# dbt_shield_v2_v23.net
KiCad netlist of a schematic drawn in EAGLE
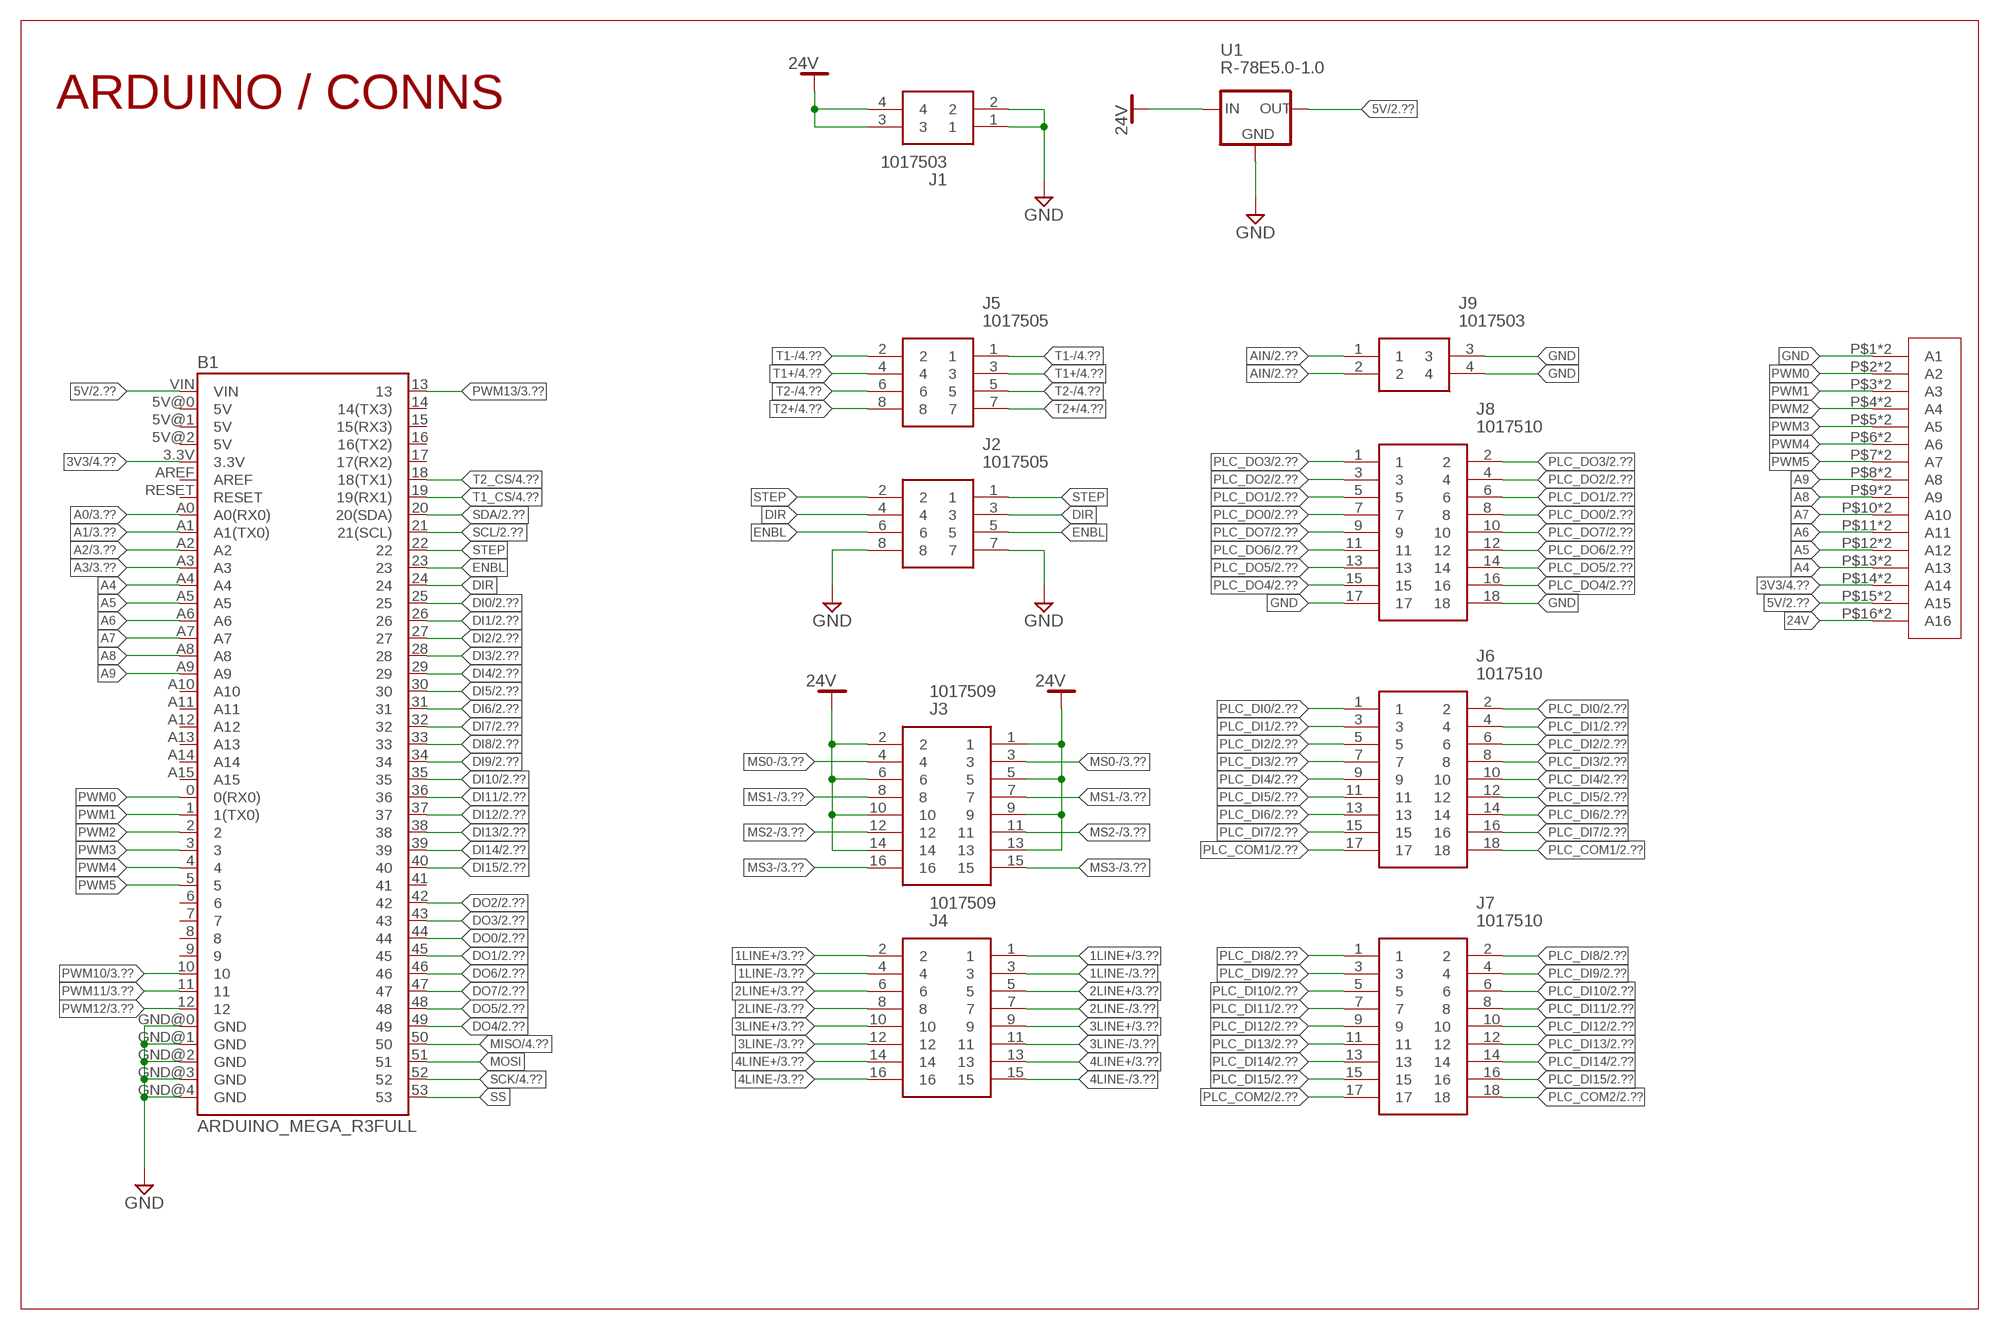
[diagram p0: schematic, sheet 1]
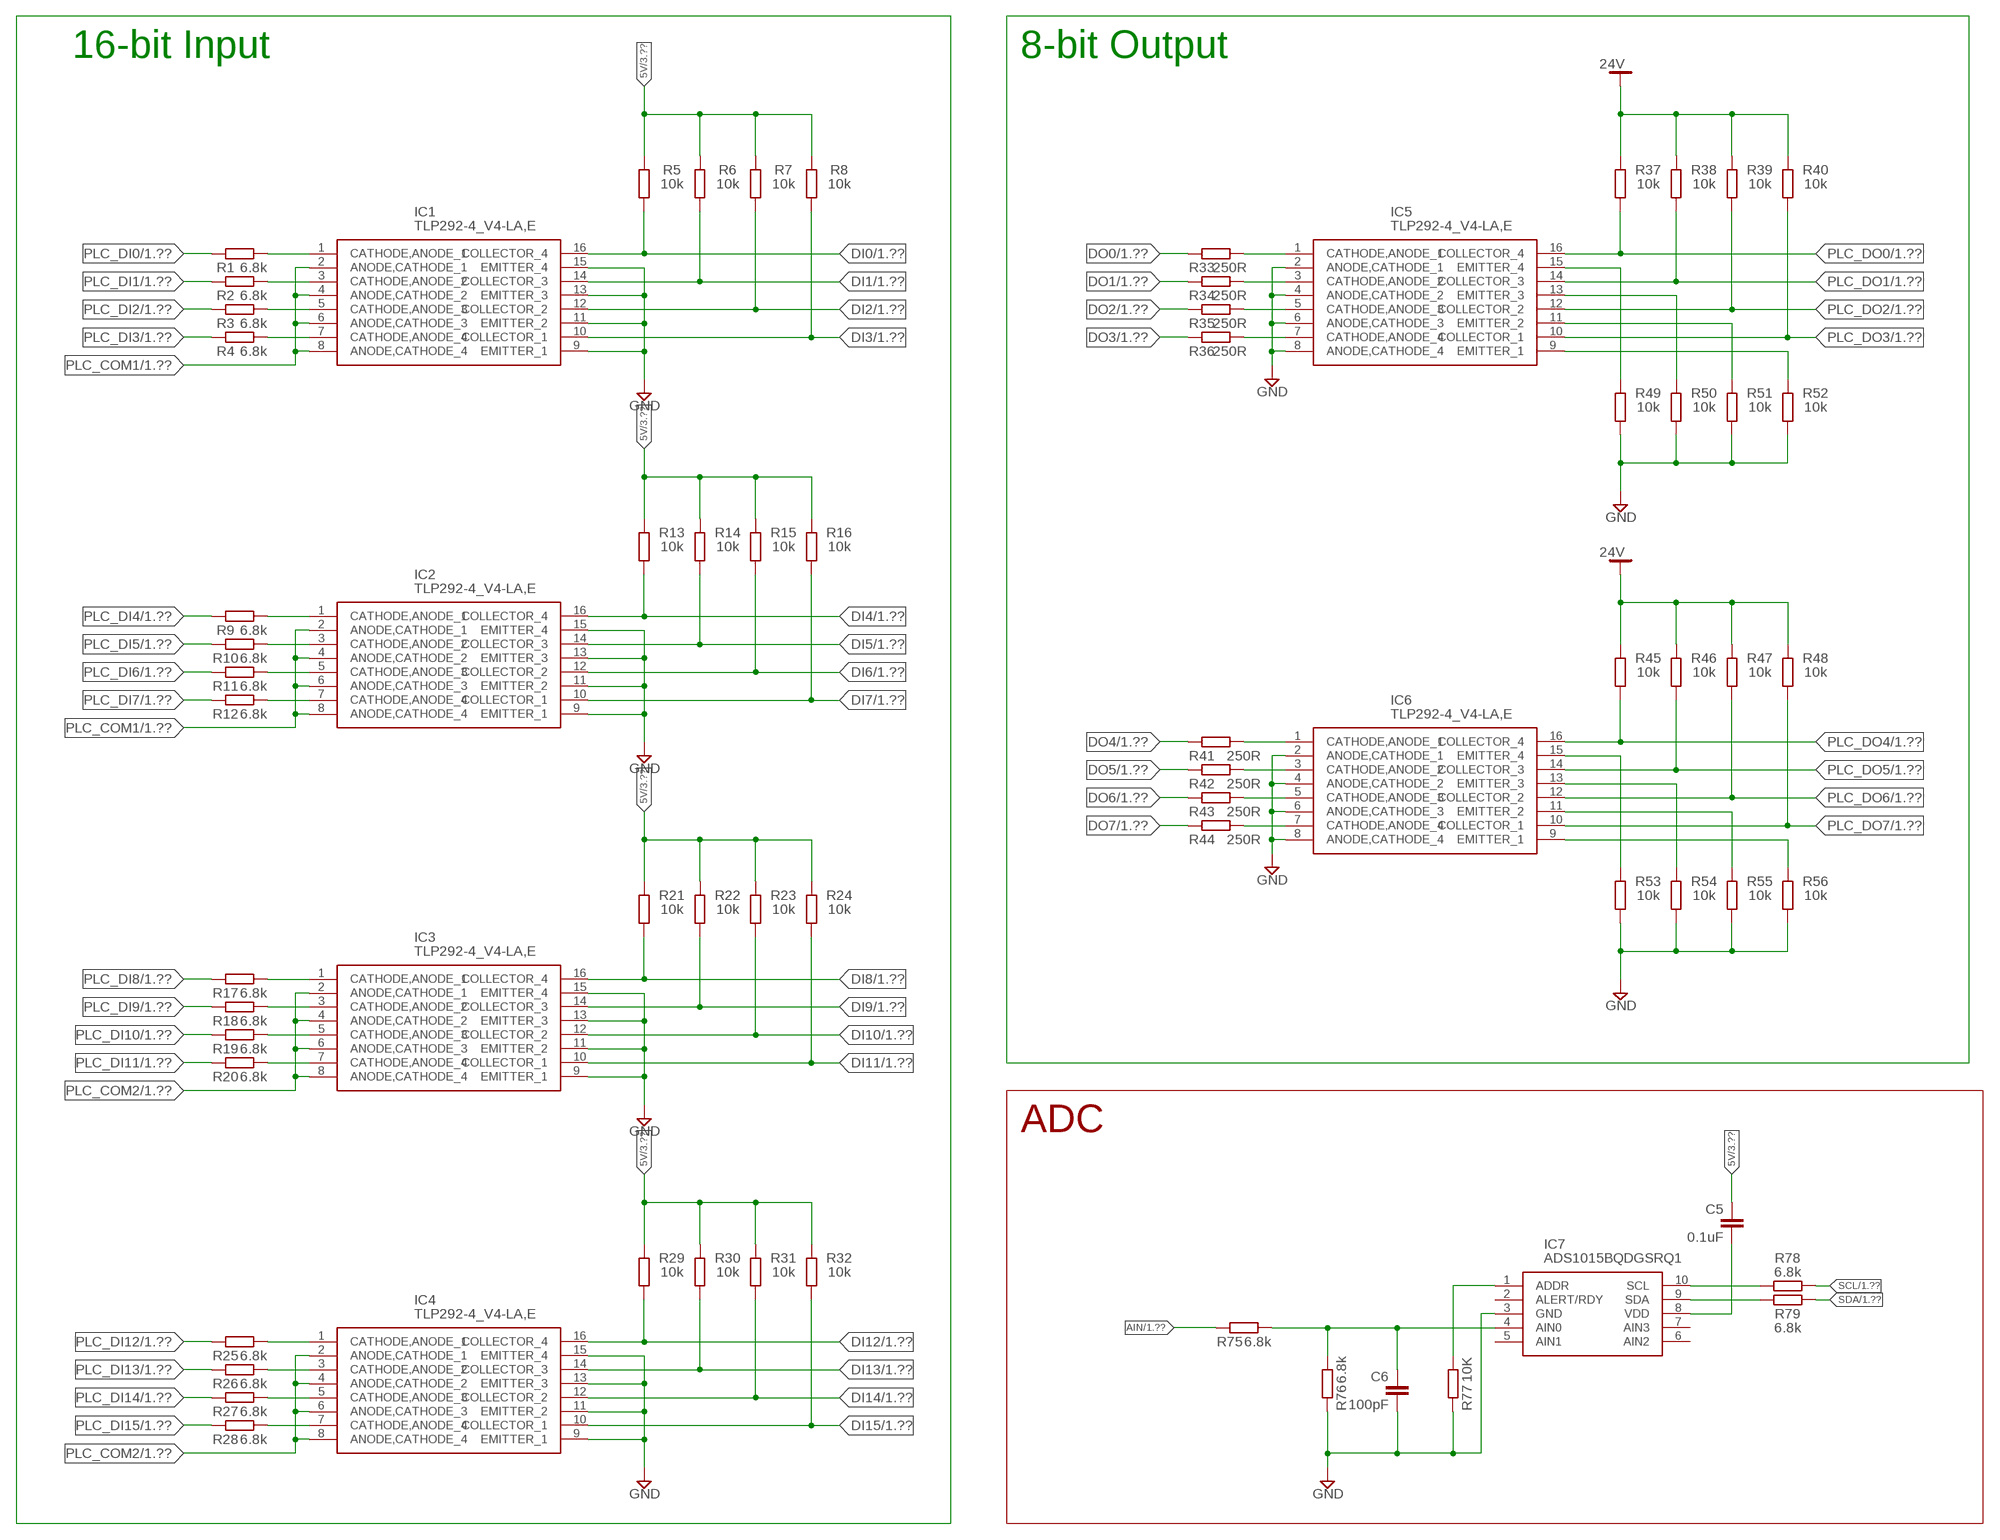
[diagram p1: schematic, sheet 2]
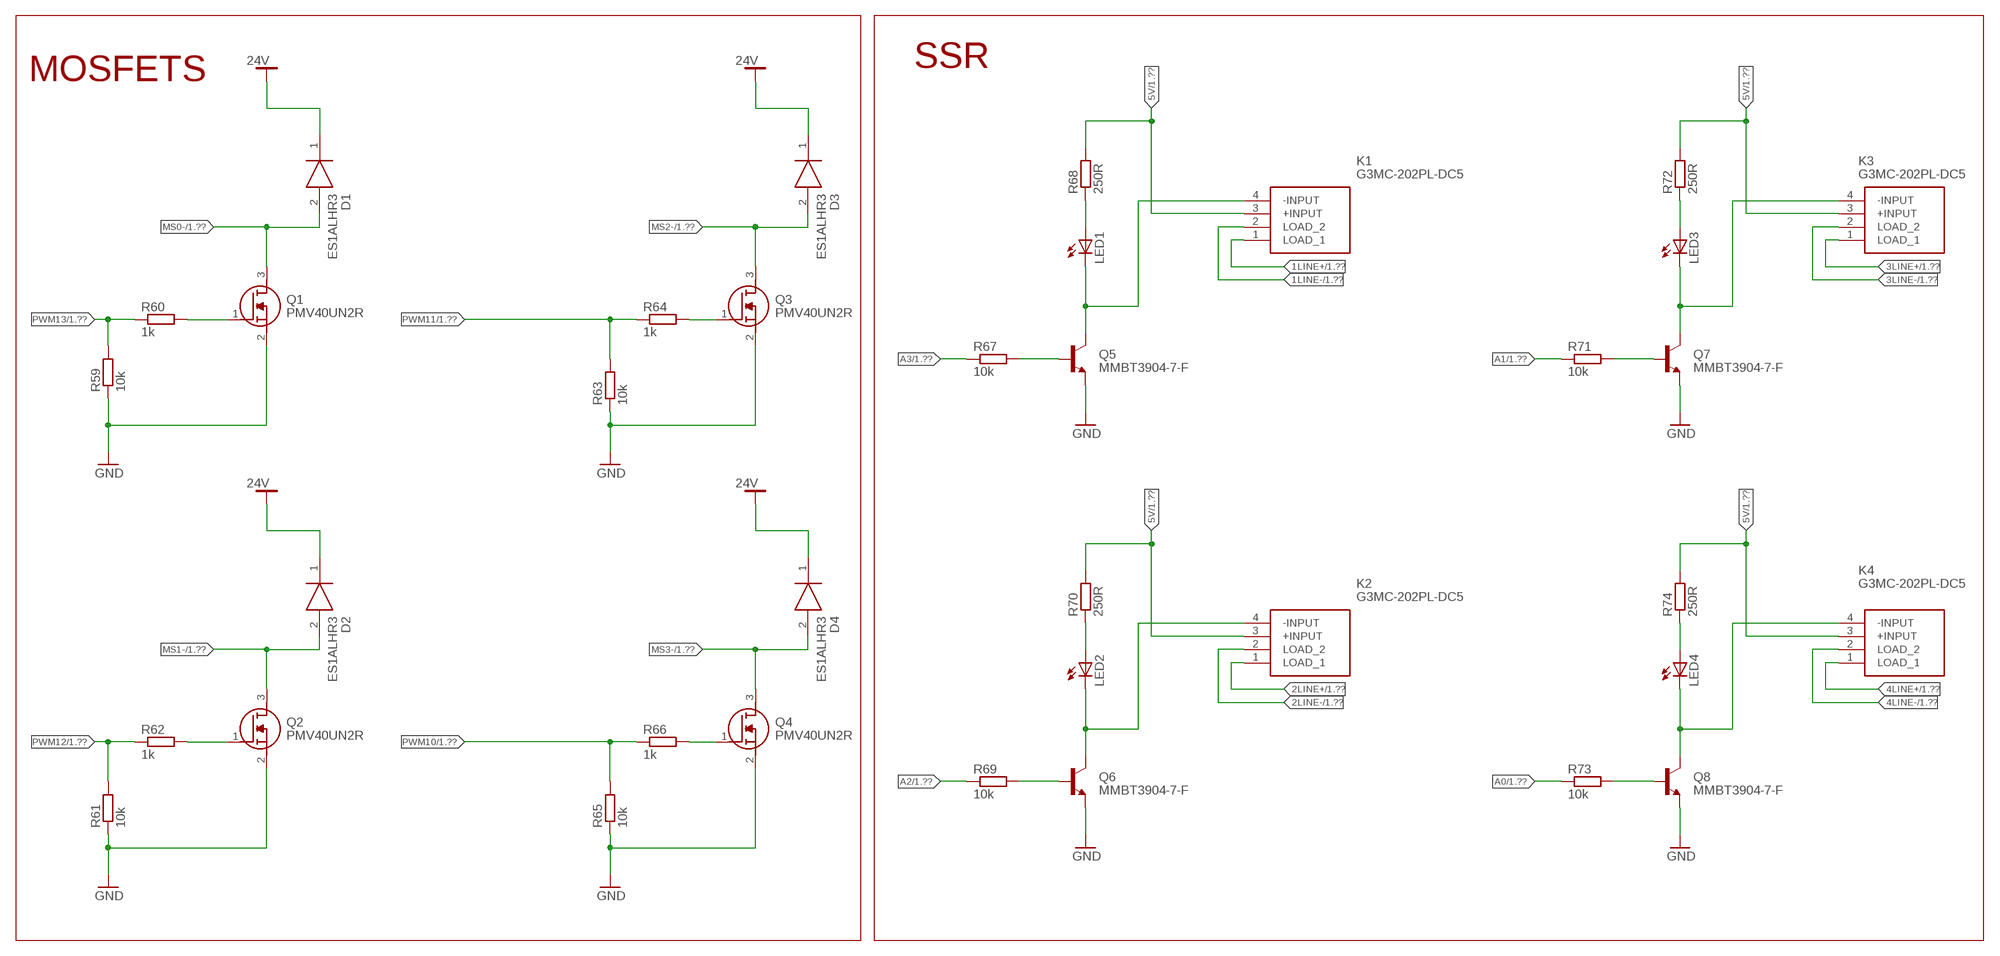
[diagram p2: schematic, sheet 3]
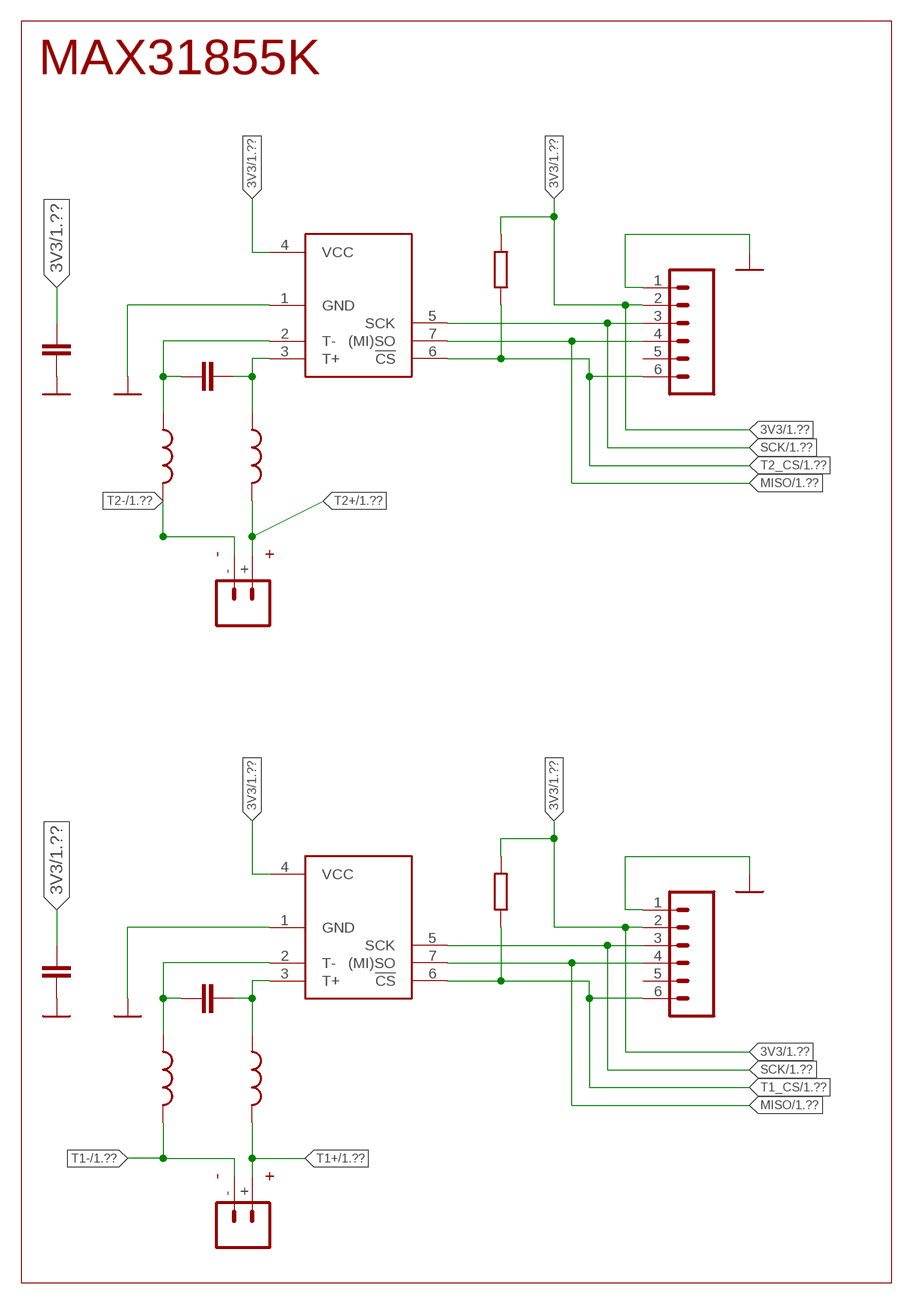
[diagram p3: schematic, sheet 4]

(export (version "E")
  (design (tool "Eeschema 10.0.6"))
  (components
    (comp (ref "C1")
      (value "0.1uF")
      (footprint "eagle-import:CAPC3216X135")
      (libsource (lib "eagle-import") (part "CCHIP-1206(3216-METRIC)_"))
    )
    (comp (ref "C2")
      (value "10 nF")
      (footprint "eagle-import:CAPC3216X135")
      (libsource (lib "eagle-import") (part "CCHIP-1206(3216-METRIC)_"))
    )
    (comp (ref "C3")
      (value "0.1uF")
      (footprint "eagle-import:CAPC3216X135")
      (libsource (lib "eagle-import") (part "CCHIP-1206(3216-METRIC)_"))
    )
    (comp (ref "C4")
      (value "10 nF")
      (footprint "eagle-import:CAPC3216X135")
      (libsource (lib "eagle-import") (part "CCHIP-1206(3216-METRIC)_"))
    )
    (comp (ref "JP1")
      (value "DNP")
      (footprint "eagle-import:1X06")
      (libsource (lib "eagle-import") (part "M06SILK_FEMALE_PTH"))
    )
    (comp (ref "JP2")
      (value "PCB_THERMOCOUPLE")
      (footprint "eagle-import:PCC-SMP")
      (libsource (lib "eagle-import") (part "PCB_THERMOCOUPLE"))
    )
    (comp (ref "JP3")
      (value "DNP")
      (footprint "eagle-import:1X06")
      (libsource (lib "eagle-import") (part "M06SILK_FEMALE_PTH"))
    )
    (comp (ref "JP4")
      (value "PCB_THERMOCOUPLE")
      (footprint "eagle-import:PCC-SMP")
      (libsource (lib "eagle-import") (part "PCB_THERMOCOUPLE"))
    )
    (comp (ref "L1")
      (value "470 OHM")
      (footprint "eagle-import:INDC3216X190")
      (fields (field (name "PROD_ID") "NDUC-12579"))
      (libsource (lib "eagle-import") (part "LCHIP-1206(3216-METRIC)_"))
    )
    (comp (ref "L2")
      (value "470 OHM")
      (footprint "eagle-import:INDC3216X190")
      (fields (field (name "PROD_ID") "NDUC-12579"))
      (libsource (lib "eagle-import") (part "LCHIP-1206(3216-METRIC)_"))
    )
    (comp (ref "L3")
      (value "470 OHM")
      (footprint "eagle-import:INDC3216X190")
      (fields (field (name "PROD_ID") "NDUC-12579"))
      (libsource (lib "eagle-import") (part "LCHIP-1206(3216-METRIC)_"))
    )
    (comp (ref "L4")
      (value "470 OHM")
      (footprint "eagle-import:INDC3216X190")
      (fields (field (name "PROD_ID") "NDUC-12579"))
      (libsource (lib "eagle-import") (part "LCHIP-1206(3216-METRIC)_"))
    )
    (comp (ref "R57")
      (value "10k")
      (footprint "eagle-import:RESC3216X70")
      (libsource (lib "eagle-import") (part "RCHIP-1206(3216-METRIC)_"))
    )
    (comp (ref "R58")
      (value "10k")
      (footprint "eagle-import:RESC3216X70")
      (libsource (lib "eagle-import") (part "RCHIP-1206(3216-METRIC)_"))
    )
    (comp (ref "U2")
      (value "MAX31855K")
      (footprint "eagle-import:SOIC8")
      (fields (field (name "PROD_ID") "IC-12578"))
      (libsource (lib "eagle-import") (part "MAX31855K"))
    )
    (comp (ref "U3")
      (value "MAX31855K")
      (footprint "eagle-import:SOIC8")
      (fields (field (name "PROD_ID") "IC-12578"))
      (libsource (lib "eagle-import") (part "MAX31855K"))
    )
    (comp (ref "C5")
      (value "0.1uF")
      (footprint "eagle-import:CAPC3216X135")
      (libsource (lib "eagle-import") (part "CCHIP-1206(3216-METRIC)_"))
    )
    (comp (ref "C6")
      (value "100pF")
      (footprint "eagle-import:CAPC3216X135")
      (libsource (lib "eagle-import") (part "CCHIP-1206(3216-METRIC)_"))
    )
    (comp (ref "IC1")
      (value "TLP292-4_V4-LA,E")
      (footprint "eagle-import:SOIC127P700X230-16N")
      (fields
        (field (name "MANUFACTURER_PART_NUMBER") "TLP292-4(V4-LA,E")
        (field (name "MOUSER_PART_NUMBER") "757-TLP292-4V4-LAE")
      )
      (libsource (lib "eagle-import") (part "TLP292-4_V4-LA,E"))
    )
    (comp (ref "IC2")
      (value "TLP292-4_V4-LA,E")
      (footprint "eagle-import:SOIC127P700X230-16N")
      (fields
        (field (name "MANUFACTURER_PART_NUMBER") "TLP292-4(V4-LA,E")
        (field (name "MOUSER_PART_NUMBER") "757-TLP292-4V4-LAE")
      )
      (libsource (lib "eagle-import") (part "TLP292-4_V4-LA,E"))
    )
    (comp (ref "IC3")
      (value "TLP292-4_V4-LA,E")
      (footprint "eagle-import:SOIC127P700X230-16N")
      (fields
        (field (name "MANUFACTURER_PART_NUMBER") "TLP292-4(V4-LA,E")
        (field (name "MOUSER_PART_NUMBER") "757-TLP292-4V4-LAE")
      )
      (libsource (lib "eagle-import") (part "TLP292-4_V4-LA,E"))
    )
    (comp (ref "IC4")
      (value "TLP292-4_V4-LA,E")
      (footprint "eagle-import:SOIC127P700X230-16N")
      (fields
        (field (name "MANUFACTURER_PART_NUMBER") "TLP292-4(V4-LA,E")
        (field (name "MOUSER_PART_NUMBER") "757-TLP292-4V4-LAE")
      )
      (libsource (lib "eagle-import") (part "TLP292-4_V4-LA,E"))
    )
    (comp (ref "IC5")
      (value "TLP292-4_V4-LA,E")
      (footprint "eagle-import:SOIC127P700X230-16N")
      (fields
        (field (name "MANUFACTURER_PART_NUMBER") "TLP292-4(V4-LA,E")
        (field (name "MOUSER_PART_NUMBER") "757-TLP292-4V4-LAE")
      )
      (libsource (lib "eagle-import") (part "TLP292-4_V4-LA,E"))
    )
    (comp (ref "IC6")
      (value "TLP292-4_V4-LA,E")
      (footprint "eagle-import:SOIC127P700X230-16N")
      (fields
        (field (name "MANUFACTURER_PART_NUMBER") "TLP292-4(V4-LA,E")
        (field (name "MOUSER_PART_NUMBER") "757-TLP292-4V4-LAE")
      )
      (libsource (lib "eagle-import") (part "TLP292-4_V4-LA,E"))
    )
    (comp (ref "IC7")
      (value "ADS1015BQDGSRQ1")
      (footprint "eagle-import:SOP50P490X110-10N")
      (fields (field (name "MOUSER_PART_NUMBER") "595-ADS1015BQDGSRQ1"))
      (libsource (lib "eagle-import") (part "ADS1015BQDGSRQ1"))
    )
    (comp (ref "R1")
      (value "6.8k")
      (footprint "eagle-import:RESC3216X70")
      (libsource (lib "eagle-import") (part "RCHIP-1206(3216-METRIC)_"))
    )
    (comp (ref "R2")
      (value "6.8k")
      (footprint "eagle-import:RESC3216X70")
      (libsource (lib "eagle-import") (part "RCHIP-1206(3216-METRIC)_"))
    )
    (comp (ref "R3")
      (value "6.8k")
      (footprint "eagle-import:RESC3216X70")
      (libsource (lib "eagle-import") (part "RCHIP-1206(3216-METRIC)_"))
    )
    (comp (ref "R4")
      (value "6.8k")
      (footprint "eagle-import:RESC3216X70")
      (libsource (lib "eagle-import") (part "RCHIP-1206(3216-METRIC)_"))
    )
    (comp (ref "R5")
      (value "10k")
      (footprint "eagle-import:RESC3216X70")
      (libsource (lib "eagle-import") (part "RCHIP-1206(3216-METRIC)_"))
    )
    (comp (ref "R6")
      (value "10k")
      (footprint "eagle-import:RESC3216X70")
      (libsource (lib "eagle-import") (part "RCHIP-1206(3216-METRIC)_"))
    )
    (comp (ref "R7")
      (value "10k")
      (footprint "eagle-import:RESC3216X70")
      (libsource (lib "eagle-import") (part "RCHIP-1206(3216-METRIC)_"))
    )
    (comp (ref "R8")
      (value "10k")
      (footprint "eagle-import:RESC3216X70")
      (libsource (lib "eagle-import") (part "RCHIP-1206(3216-METRIC)_"))
    )
    (comp (ref "R9")
      (value "6.8k")
      (footprint "eagle-import:RESC3216X70")
      (libsource (lib "eagle-import") (part "RCHIP-1206(3216-METRIC)_"))
    )
    (comp (ref "R10")
      (value "6.8k")
      (footprint "eagle-import:RESC3216X70")
      (libsource (lib "eagle-import") (part "RCHIP-1206(3216-METRIC)_"))
    )
    (comp (ref "R11")
      (value "6.8k")
      (footprint "eagle-import:RESC3216X70")
      (libsource (lib "eagle-import") (part "RCHIP-1206(3216-METRIC)_"))
    )
    (comp (ref "R12")
      (value "6.8k")
      (footprint "eagle-import:RESC3216X70")
      (libsource (lib "eagle-import") (part "RCHIP-1206(3216-METRIC)_"))
    )
    (comp (ref "R13")
      (value "10k")
      (footprint "eagle-import:RESC3216X70")
      (libsource (lib "eagle-import") (part "RCHIP-1206(3216-METRIC)_"))
    )
    (comp (ref "R14")
      (value "10k")
      (footprint "eagle-import:RESC3216X70")
      (libsource (lib "eagle-import") (part "RCHIP-1206(3216-METRIC)_"))
    )
    (comp (ref "R15")
      (value "10k")
      (footprint "eagle-import:RESC3216X70")
      (libsource (lib "eagle-import") (part "RCHIP-1206(3216-METRIC)_"))
    )
    (comp (ref "R16")
      (value "10k")
      (footprint "eagle-import:RESC3216X70")
      (libsource (lib "eagle-import") (part "RCHIP-1206(3216-METRIC)_"))
    )
    (comp (ref "R17")
      (value "6.8k")
      (footprint "eagle-import:RESC3216X70")
      (libsource (lib "eagle-import") (part "RCHIP-1206(3216-METRIC)_"))
    )
    (comp (ref "R18")
      (value "6.8k")
      (footprint "eagle-import:RESC3216X70")
      (libsource (lib "eagle-import") (part "RCHIP-1206(3216-METRIC)_"))
    )
    (comp (ref "R19")
      (value "6.8k")
      (footprint "eagle-import:RESC3216X70")
      (libsource (lib "eagle-import") (part "RCHIP-1206(3216-METRIC)_"))
    )
    (comp (ref "R20")
      (value "6.8k")
      (footprint "eagle-import:RESC3216X70")
      (libsource (lib "eagle-import") (part "RCHIP-1206(3216-METRIC)_"))
    )
    (comp (ref "R21")
      (value "10k")
      (footprint "eagle-import:RESC3216X70")
      (libsource (lib "eagle-import") (part "RCHIP-1206(3216-METRIC)_"))
    )
    (comp (ref "R22")
      (value "10k")
      (footprint "eagle-import:RESC3216X70")
      (libsource (lib "eagle-import") (part "RCHIP-1206(3216-METRIC)_"))
    )
    (comp (ref "R23")
      (value "10k")
      (footprint "eagle-import:RESC3216X70")
      (libsource (lib "eagle-import") (part "RCHIP-1206(3216-METRIC)_"))
    )
    (comp (ref "R24")
      (value "10k")
      (footprint "eagle-import:RESC3216X70")
      (libsource (lib "eagle-import") (part "RCHIP-1206(3216-METRIC)_"))
    )
    (comp (ref "R25")
      (value "6.8k")
      (footprint "eagle-import:RESC3216X70")
      (libsource (lib "eagle-import") (part "RCHIP-1206(3216-METRIC)_"))
    )
    (comp (ref "R26")
      (value "6.8k")
      (footprint "eagle-import:RESC3216X70")
      (libsource (lib "eagle-import") (part "RCHIP-1206(3216-METRIC)_"))
    )
    (comp (ref "R27")
      (value "6.8k")
      (footprint "eagle-import:RESC3216X70")
      (libsource (lib "eagle-import") (part "RCHIP-1206(3216-METRIC)_"))
    )
    (comp (ref "R28")
      (value "6.8k")
      (footprint "eagle-import:RESC3216X70")
      (libsource (lib "eagle-import") (part "RCHIP-1206(3216-METRIC)_"))
    )
    (comp (ref "R29")
      (value "10k")
      (footprint "eagle-import:RESC3216X70")
      (libsource (lib "eagle-import") (part "RCHIP-1206(3216-METRIC)_"))
    )
    (comp (ref "R30")
      (value "10k")
      (footprint "eagle-import:RESC3216X70")
      (libsource (lib "eagle-import") (part "RCHIP-1206(3216-METRIC)_"))
    )
    (comp (ref "R31")
      (value "10k")
      (footprint "eagle-import:RESC3216X70")
      (libsource (lib "eagle-import") (part "RCHIP-1206(3216-METRIC)_"))
    )
    (comp (ref "R32")
      (value "10k")
      (footprint "eagle-import:RESC3216X70")
      (libsource (lib "eagle-import") (part "RCHIP-1206(3216-METRIC)_"))
    )
    (comp (ref "R33")
      (value "250R")
      (footprint "eagle-import:RESC3216X70")
      (libsource (lib "eagle-import") (part "RCHIP-1206(3216-METRIC)_"))
    )
    (comp (ref "R34")
      (value "250R")
      (footprint "eagle-import:RESC3216X70")
      (libsource (lib "eagle-import") (part "RCHIP-1206(3216-METRIC)_"))
    )
    (comp (ref "R35")
      (value "250R")
      (footprint "eagle-import:RESC3216X70")
      (libsource (lib "eagle-import") (part "RCHIP-1206(3216-METRIC)_"))
    )
    (comp (ref "R36")
      (value "250R")
      (footprint "eagle-import:RESC3216X70")
      (libsource (lib "eagle-import") (part "RCHIP-1206(3216-METRIC)_"))
    )
    (comp (ref "R37")
      (value "10k")
      (footprint "eagle-import:RESC3216X70")
      (libsource (lib "eagle-import") (part "RCHIP-1206(3216-METRIC)_"))
    )
    (comp (ref "R38")
      (value "10k")
      (footprint "eagle-import:RESC3216X70")
      (libsource (lib "eagle-import") (part "RCHIP-1206(3216-METRIC)_"))
    )
    (comp (ref "R39")
      (value "10k")
      (footprint "eagle-import:RESC3216X70")
      (libsource (lib "eagle-import") (part "RCHIP-1206(3216-METRIC)_"))
    )
    (comp (ref "R40")
      (value "10k")
      (footprint "eagle-import:RESC3216X70")
      (libsource (lib "eagle-import") (part "RCHIP-1206(3216-METRIC)_"))
    )
    (comp (ref "R41")
      (value "250R")
      (footprint "eagle-import:RESC3216X70")
      (libsource (lib "eagle-import") (part "RCHIP-1206(3216-METRIC)_"))
    )
    (comp (ref "R42")
      (value "250R")
      (footprint "eagle-import:RESC3216X70")
      (libsource (lib "eagle-import") (part "RCHIP-1206(3216-METRIC)_"))
    )
    (comp (ref "R43")
      (value "250R")
      (footprint "eagle-import:RESC3216X70")
      (libsource (lib "eagle-import") (part "RCHIP-1206(3216-METRIC)_"))
    )
    (comp (ref "R44")
      (value "250R")
      (footprint "eagle-import:RESC3216X70")
      (libsource (lib "eagle-import") (part "RCHIP-1206(3216-METRIC)_"))
    )
    (comp (ref "R45")
      (value "10k")
      (footprint "eagle-import:RESC3216X70")
      (libsource (lib "eagle-import") (part "RCHIP-1206(3216-METRIC)_"))
    )
    (comp (ref "R46")
      (value "10k")
      (footprint "eagle-import:RESC3216X70")
      (libsource (lib "eagle-import") (part "RCHIP-1206(3216-METRIC)_"))
    )
    (comp (ref "R47")
      (value "10k")
      (footprint "eagle-import:RESC3216X70")
      (libsource (lib "eagle-import") (part "RCHIP-1206(3216-METRIC)_"))
    )
    (comp (ref "R48")
      (value "10k")
      (footprint "eagle-import:RESC3216X70")
      (libsource (lib "eagle-import") (part "RCHIP-1206(3216-METRIC)_"))
    )
    (comp (ref "R49")
      (value "10k")
      (footprint "eagle-import:RESC3216X70")
      (libsource (lib "eagle-import") (part "RCHIP-1206(3216-METRIC)_"))
    )
    (comp (ref "R50")
      (value "10k")
      (footprint "eagle-import:RESC3216X70")
      (libsource (lib "eagle-import") (part "RCHIP-1206(3216-METRIC)_"))
    )
    (comp (ref "R51")
      (value "10k")
      (footprint "eagle-import:RESC3216X70")
      (libsource (lib "eagle-import") (part "RCHIP-1206(3216-METRIC)_"))
    )
    (comp (ref "R52")
      (value "10k")
      (footprint "eagle-import:RESC3216X70")
      (libsource (lib "eagle-import") (part "RCHIP-1206(3216-METRIC)_"))
    )
    (comp (ref "R53")
      (value "10k")
      (footprint "eagle-import:RESC3216X70")
      (libsource (lib "eagle-import") (part "RCHIP-1206(3216-METRIC)_"))
    )
    (comp (ref "R54")
      (value "10k")
      (footprint "eagle-import:RESC3216X70")
      (libsource (lib "eagle-import") (part "RCHIP-1206(3216-METRIC)_"))
    )
    (comp (ref "R55")
      (value "10k")
      (footprint "eagle-import:RESC3216X70")
      (libsource (lib "eagle-import") (part "RCHIP-1206(3216-METRIC)_"))
    )
    (comp (ref "R56")
      (value "10k")
      (footprint "eagle-import:RESC3216X70")
      (libsource (lib "eagle-import") (part "RCHIP-1206(3216-METRIC)_"))
    )
    (comp (ref "R75")
      (value "6.8k")
      (footprint "eagle-import:RESC3216X70")
      (libsource (lib "eagle-import") (part "RCHIP-1206(3216-METRIC)_"))
    )
    (comp (ref "R76")
      (value "6.8k")
      (footprint "eagle-import:RESC3216X70")
      (libsource (lib "eagle-import") (part "RCHIP-1206(3216-METRIC)_"))
    )
    (comp (ref "R77")
      (value "10K")
      (footprint "eagle-import:RESC3216X70")
      (libsource (lib "eagle-import") (part "RCHIP-1206(3216-METRIC)_"))
    )
    (comp (ref "R78")
      (value "6.8k")
      (footprint "eagle-import:RESC3216X70")
      (libsource (lib "eagle-import") (part "RCHIP-1206(3216-METRIC)_"))
    )
    (comp (ref "R79")
      (value "6.8k")
      (footprint "eagle-import:RESC3216X70")
      (libsource (lib "eagle-import") (part "RCHIP-1206(3216-METRIC)_"))
    )
    (comp (ref "B1")
      (value "ARDUINO_MEGA_R3FULL")
      (footprint "eagle-import:ARDUINO_MEGA")
      (libsource (lib "eagle-import") (part "ARDUINO_MEGA_R3FULL"))
    )
    (comp (ref "J1")
      (value "1017503")
      (footprint "eagle-import:1017503")
      (fields (field (name "MOUSER_PART_NUMBER") "651-1017503"))
      (libsource (lib "eagle-import") (part "1017503"))
    )
    (comp (ref "J2")
      (value "1017505")
      (footprint "eagle-import:1017505")
      (fields (field (name "MOUSER_PART_NUMBER") "651-1017505") (field (name "RS_PART_NUMBER") "1753922"))
      (libsource (lib "eagle-import") (part "1017505"))
    )
    (comp (ref "J3")
      (value "1017509")
      (footprint "eagle-import:1017509")
      (fields (field (name "MOUSER_PART_NUMBER") "651-1017509") (field (name "RS_PART_NUMBER") "1753943P"))
      (libsource (lib "eagle-import") (part "1017509"))
    )
    (comp (ref "J4")
      (value "1017509")
      (footprint "eagle-import:1017509")
      (fields (field (name "MOUSER_PART_NUMBER") "651-1017509") (field (name "RS_PART_NUMBER") "1753943P"))
      (libsource (lib "eagle-import") (part "1017509"))
    )
    (comp (ref "J5")
      (value "1017505")
      (footprint "eagle-import:1017505")
      (fields (field (name "MOUSER_PART_NUMBER") "651-1017505") (field (name "RS_PART_NUMBER") "1753922"))
      (libsource (lib "eagle-import") (part "1017505"))
    )
    (comp (ref "J6")
      (value "1017510")
      (footprint "eagle-import:SHDR18W120P870X508_2X9_4652X18")
      (fields (field (name "MOUSER_PART_NUMBER") "651-1017510") (field (name "RS_PART_NUMBER") "1753946P"))
      (libsource (lib "eagle-import") (part "1017510"))
    )
    (comp (ref "J7")
      (value "1017510")
      (footprint "eagle-import:SHDR18W120P870X508_2X9_4652X18")
      (fields (field (name "MOUSER_PART_NUMBER") "651-1017510") (field (name "RS_PART_NUMBER") "1753946P"))
      (libsource (lib "eagle-import") (part "1017510"))
    )
    (comp (ref "J8")
      (value "1017510")
      (footprint "eagle-import:SHDR18W120P870X508_2X9_4652X18")
      (fields (field (name "MOUSER_PART_NUMBER") "651-1017510") (field (name "RS_PART_NUMBER") "1753946P"))
      (libsource (lib "eagle-import") (part "1017510"))
    )
    (comp (ref "J9")
      (value "1017503")
      (footprint "eagle-import:1017503")
      (fields (field (name "MOUSER_PART_NUMBER") "651-1017503"))
      (libsource (lib "eagle-import") (part "1017503"))
    )
    (comp (ref "U$1")
      (value "1861991")
      (footprint "eagle-import:1861991")
      (libsource (lib "eagle-import") (part "1861991"))
    )
    (comp (ref "U1")
      (value "R-78E5.0-1.0")
      (footprint "eagle-import:DC-DC_CONVERTER_78XX")
      (libsource (lib "eagle-import") (part "R-78E5.0-1.0"))
    )
    (comp (ref "D1")
      (value "ES1ALHR3")
      (footprint "eagle-import:SODFL3618X143N")
      (fields (field (name "MOUSER_PART_NUMBER") "821-ES1ALHR3"))
      (libsource (lib "eagle-import") (part "ES1ALHR3"))
    )
    (comp (ref "D2")
      (value "ES1ALHR3")
      (footprint "eagle-import:SODFL3618X143N")
      (fields (field (name "MOUSER_PART_NUMBER") "821-ES1ALHR3"))
      (libsource (lib "eagle-import") (part "ES1ALHR3"))
    )
    (comp (ref "D3")
      (value "ES1ALHR3")
      (footprint "eagle-import:SODFL3618X143N")
      (fields (field (name "MOUSER_PART_NUMBER") "821-ES1ALHR3"))
      (libsource (lib "eagle-import") (part "ES1ALHR3"))
    )
    (comp (ref "D4")
      (value "ES1ALHR3")
      (footprint "eagle-import:SODFL3618X143N")
      (fields (field (name "MOUSER_PART_NUMBER") "821-ES1ALHR3"))
      (libsource (lib "eagle-import") (part "ES1ALHR3"))
    )
    (comp (ref "K1")
      (value "G3MC-202PL-DC5")
      (footprint "eagle-import:G3MC202PLDC5")
      (fields (field (name "MOUSER_PART_NUMBER") "653-G3MC-202PL-DC5"))
      (libsource (lib "eagle-import") (part "G3MC-202PL-DC5"))
    )
    (comp (ref "K2")
      (value "G3MC-202PL-DC5")
      (footprint "eagle-import:G3MC202PLDC5")
      (fields (field (name "MOUSER_PART_NUMBER") "653-G3MC-202PL-DC5"))
      (libsource (lib "eagle-import") (part "G3MC-202PL-DC5"))
    )
    (comp (ref "K3")
      (value "G3MC-202PL-DC5")
      (footprint "eagle-import:G3MC202PLDC5")
      (fields (field (name "MOUSER_PART_NUMBER") "653-G3MC-202PL-DC5"))
      (libsource (lib "eagle-import") (part "G3MC-202PL-DC5"))
    )
    (comp (ref "K4")
      (value "G3MC-202PL-DC5")
      (footprint "eagle-import:G3MC202PLDC5")
      (fields (field (name "MOUSER_PART_NUMBER") "653-G3MC-202PL-DC5"))
      (libsource (lib "eagle-import") (part "G3MC-202PL-DC5"))
    )
    (comp (ref "LED1")
      (value "LEDCHIPLED_1206")
      (footprint "eagle-import:CHIPLED_1206")
      (libsource (lib "eagle-import") (part "LEDCHIPLED_1206"))
    )
    (comp (ref "LED2")
      (value "LEDCHIPLED_1206")
      (footprint "eagle-import:CHIPLED_1206")
      (libsource (lib "eagle-import") (part "LEDCHIPLED_1206"))
    )
    (comp (ref "LED3")
      (value "LEDCHIPLED_1206")
      (footprint "eagle-import:CHIPLED_1206")
      (libsource (lib "eagle-import") (part "LEDCHIPLED_1206"))
    )
    (comp (ref "LED4")
      (value "LEDCHIPLED_1206")
      (footprint "eagle-import:CHIPLED_1206")
      (libsource (lib "eagle-import") (part "LEDCHIPLED_1206"))
    )
    (comp (ref "Q1")
      (value "PMV40UN2R")
      (footprint "eagle-import:SOT95P230X110-3N")
      (fields (field (name "MOUSER_PART_NUMBER") "771-PMV40UN2R") (field (name "RS_PART_NUMBER") "1362196P"))
      (libsource (lib "eagle-import") (part "PMV40UN2R"))
    )
    (comp (ref "Q2")
      (value "PMV40UN2R")
      (footprint "eagle-import:SOT95P230X110-3N")
      (fields (field (name "MOUSER_PART_NUMBER") "771-PMV40UN2R") (field (name "RS_PART_NUMBER") "1362196P"))
      (libsource (lib "eagle-import") (part "PMV40UN2R"))
    )
    (comp (ref "Q3")
      (value "PMV40UN2R")
      (footprint "eagle-import:SOT95P230X110-3N")
      (fields (field (name "MOUSER_PART_NUMBER") "771-PMV40UN2R") (field (name "RS_PART_NUMBER") "1362196P"))
      (libsource (lib "eagle-import") (part "PMV40UN2R"))
    )
    (comp (ref "Q4")
      (value "PMV40UN2R")
      (footprint "eagle-import:SOT95P230X110-3N")
      (fields (field (name "MOUSER_PART_NUMBER") "771-PMV40UN2R") (field (name "RS_PART_NUMBER") "1362196P"))
      (libsource (lib "eagle-import") (part "PMV40UN2R"))
    )
    (comp (ref "Q5")
      (value "MMBT3904-7-F")
      (footprint "eagle-import:SOT95P230X110-3N1")
      (fields (field (name "MF") "Diodes Inc."))
      (libsource (lib "eagle-import") (part "MMBT3904-7-F"))
    )
    (comp (ref "Q6")
      (value "MMBT3904-7-F")
      (footprint "eagle-import:SOT95P230X110-3N1")
      (fields (field (name "MF") "Diodes Inc."))
      (libsource (lib "eagle-import") (part "MMBT3904-7-F"))
    )
    (comp (ref "Q7")
      (value "MMBT3904-7-F")
      (footprint "eagle-import:SOT95P230X110-3N1")
      (fields (field (name "MF") "Diodes Inc."))
      (libsource (lib "eagle-import") (part "MMBT3904-7-F"))
    )
    (comp (ref "Q8")
      (value "MMBT3904-7-F")
      (footprint "eagle-import:SOT95P230X110-3N1")
      (fields (field (name "MF") "Diodes Inc."))
      (libsource (lib "eagle-import") (part "MMBT3904-7-F"))
    )
    (comp (ref "R59")
      (value "10k")
      (footprint "eagle-import:RESC3216X70")
      (libsource (lib "eagle-import") (part "RCHIP-1206(3216-METRIC)_"))
    )
    (comp (ref "R60")
      (value "1k")
      (footprint "eagle-import:RESC3216X70")
      (libsource (lib "eagle-import") (part "RCHIP-1206(3216-METRIC)_"))
    )
    (comp (ref "R61")
      (value "10k")
      (footprint "eagle-import:RESC3216X70")
      (libsource (lib "eagle-import") (part "RCHIP-1206(3216-METRIC)_"))
    )
    (comp (ref "R62")
      (value "1k")
      (footprint "eagle-import:RESC3216X70")
      (libsource (lib "eagle-import") (part "RCHIP-1206(3216-METRIC)_"))
    )
    (comp (ref "R63")
      (value "10k")
      (footprint "eagle-import:RESC3216X70")
      (libsource (lib "eagle-import") (part "RCHIP-1206(3216-METRIC)_"))
    )
    (comp (ref "R64")
      (value "1k")
      (footprint "eagle-import:RESC3216X70")
      (libsource (lib "eagle-import") (part "RCHIP-1206(3216-METRIC)_"))
    )
    (comp (ref "R65")
      (value "10k")
      (footprint "eagle-import:RESC3216X70")
      (libsource (lib "eagle-import") (part "RCHIP-1206(3216-METRIC)_"))
    )
    (comp (ref "R66")
      (value "1k")
      (footprint "eagle-import:RESC3216X70")
      (libsource (lib "eagle-import") (part "RCHIP-1206(3216-METRIC)_"))
    )
    (comp (ref "R67")
      (value "10k")
      (footprint "eagle-import:RESC3216X70")
      (libsource (lib "eagle-import") (part "RCHIP-1206(3216-METRIC)_"))
    )
    (comp (ref "R68")
      (value "250R")
      (footprint "eagle-import:RESC3216X70")
      (libsource (lib "eagle-import") (part "RCHIP-1206(3216-METRIC)_"))
    )
    (comp (ref "R69")
      (value "10k")
      (footprint "eagle-import:RESC3216X70")
      (libsource (lib "eagle-import") (part "RCHIP-1206(3216-METRIC)_"))
    )
    (comp (ref "R70")
      (value "250R")
      (footprint "eagle-import:RESC3216X70")
      (libsource (lib "eagle-import") (part "RCHIP-1206(3216-METRIC)_"))
    )
    (comp (ref "R71")
      (value "10k")
      (footprint "eagle-import:RESC3216X70")
      (libsource (lib "eagle-import") (part "RCHIP-1206(3216-METRIC)_"))
    )
    (comp (ref "R72")
      (value "250R")
      (footprint "eagle-import:RESC3216X70")
      (libsource (lib "eagle-import") (part "RCHIP-1206(3216-METRIC)_"))
    )
    (comp (ref "R73")
      (value "10k")
      (footprint "eagle-import:RESC3216X70")
      (libsource (lib "eagle-import") (part "RCHIP-1206(3216-METRIC)_"))
    )
    (comp (ref "R74")
      (value "250R")
      (footprint "eagle-import:RESC3216X70")
      (libsource (lib "eagle-import") (part "RCHIP-1206(3216-METRIC)_"))
    )
  )
  (nets
    (net (code "1") (name "1LINE+") (class "Default")
      (node (ref "J4") (pin "1") (pinfunction "1_1") (pintype "bidirectional"))
      (node (ref "J4") (pin "2") (pinfunction "2_2") (pintype "bidirectional"))
      (node (ref "K1") (pin "1") (pinfunction "LOAD_1_1") (pintype "bidirectional"))
    )
    (net (code "2") (name "1LINE-") (class "Default")
      (node (ref "J4") (pin "3") (pinfunction "3_3") (pintype "bidirectional"))
      (node (ref "J4") (pin "4") (pinfunction "4_4") (pintype "bidirectional"))
      (node (ref "K1") (pin "2") (pinfunction "LOAD_2_2") (pintype "bidirectional"))
    )
    (net (code "3") (name "2LINE+") (class "Default")
      (node (ref "J4") (pin "5") (pinfunction "5_5") (pintype "bidirectional"))
      (node (ref "J4") (pin "6") (pinfunction "6_6") (pintype "bidirectional"))
      (node (ref "K2") (pin "1") (pinfunction "LOAD_1_1") (pintype "bidirectional"))
    )
    (net (code "4") (name "2LINE-") (class "Default")
      (node (ref "J4") (pin "7") (pinfunction "7_7") (pintype "bidirectional"))
      (node (ref "J4") (pin "8") (pinfunction "8_8") (pintype "bidirectional"))
      (node (ref "K2") (pin "2") (pinfunction "LOAD_2_2") (pintype "bidirectional"))
    )
    (net (code "5") (name "3LINE+") (class "Default")
      (node (ref "J4") (pin "10") (pinfunction "10_10") (pintype "bidirectional"))
      (node (ref "J4") (pin "9") (pinfunction "9_9") (pintype "bidirectional"))
      (node (ref "K3") (pin "1") (pinfunction "LOAD_1_1") (pintype "bidirectional"))
    )
    (net (code "6") (name "3LINE-") (class "Default")
      (node (ref "J4") (pin "11") (pinfunction "11_11") (pintype "bidirectional"))
      (node (ref "J4") (pin "12") (pinfunction "12_12") (pintype "bidirectional"))
      (node (ref "K3") (pin "2") (pinfunction "LOAD_2_2") (pintype "bidirectional"))
    )
    (net (code "7") (name "3V3") (class "Default")
      (node (ref "B1") (pin "3.3V") (pinfunction "3.3V_3.3V") (pintype "bidirectional"))
      (node (ref "C1") (pin "1") (pinfunction "1_1") (pintype "passive"))
      (node (ref "C3") (pin "1") (pinfunction "1_1") (pintype "passive"))
      (node (ref "JP1") (pin "2") (pinfunction "2_2") (pintype "passive"))
      (node (ref "JP3") (pin "2") (pinfunction "2_2") (pintype "passive"))
      (node (ref "R57") (pin "2") (pinfunction "2_2") (pintype "passive"))
      (node (ref "R58") (pin "2") (pinfunction "2_2") (pintype "passive"))
      (node (ref "U$1") (pin "P$14") (pinfunction "A14_P$14") (pintype "bidirectional"))
      (node (ref "U$1") (pin "P$30") (pinfunction "A14_P$30") (pintype "bidirectional"))
      (node (ref "U2") (pin "4") (pinfunction "VCC_4") (pintype "bidirectional"))
      (node (ref "U3") (pin "4") (pinfunction "VCC_4") (pintype "bidirectional"))
    )
    (net (code "8") (name "4LINE+") (class "Default")
      (node (ref "J4") (pin "13") (pinfunction "13_13") (pintype "bidirectional"))
      (node (ref "J4") (pin "14") (pinfunction "14_14") (pintype "bidirectional"))
      (node (ref "K4") (pin "1") (pinfunction "LOAD_1_1") (pintype "bidirectional"))
    )
    (net (code "9") (name "4LINE-") (class "Default")
      (node (ref "J4") (pin "15") (pinfunction "15_15") (pintype "bidirectional"))
      (node (ref "J4") (pin "16") (pinfunction "16_16") (pintype "bidirectional"))
      (node (ref "K4") (pin "2") (pinfunction "LOAD_2_2") (pintype "bidirectional"))
    )
    (net (code "10") (name "5V") (class "Default")
      (node (ref "B1") (pin "VIN") (pinfunction "VIN_VIN") (pintype "bidirectional"))
      (node (ref "C5") (pin "1") (pinfunction "1_1") (pintype "passive"))
      (node (ref "K1") (pin "3") (pinfunction "+INPUT_3") (pintype "bidirectional"))
      (node (ref "K2") (pin "3") (pinfunction "+INPUT_3") (pintype "bidirectional"))
      (node (ref "K3") (pin "3") (pinfunction "+INPUT_3") (pintype "bidirectional"))
      (node (ref "K4") (pin "3") (pinfunction "+INPUT_3") (pintype "bidirectional"))
      (node (ref "R13") (pin "2") (pinfunction "2_2") (pintype "passive"))
      (node (ref "R14") (pin "2") (pinfunction "2_2") (pintype "passive"))
      (node (ref "R15") (pin "2") (pinfunction "2_2") (pintype "passive"))
      (node (ref "R16") (pin "2") (pinfunction "2_2") (pintype "passive"))
      (node (ref "R21") (pin "2") (pinfunction "2_2") (pintype "passive"))
      (node (ref "R22") (pin "2") (pinfunction "2_2") (pintype "passive"))
      (node (ref "R23") (pin "2") (pinfunction "2_2") (pintype "passive"))
      (node (ref "R24") (pin "2") (pinfunction "2_2") (pintype "passive"))
      (node (ref "R29") (pin "2") (pinfunction "2_2") (pintype "passive"))
      (node (ref "R30") (pin "2") (pinfunction "2_2") (pintype "passive"))
      (node (ref "R31") (pin "2") (pinfunction "2_2") (pintype "passive"))
      (node (ref "R32") (pin "2") (pinfunction "2_2") (pintype "passive"))
      (node (ref "R5") (pin "2") (pinfunction "2_2") (pintype "passive"))
      (node (ref "R6") (pin "2") (pinfunction "2_2") (pintype "passive"))
      (node (ref "R68") (pin "2") (pinfunction "2_2") (pintype "passive"))
      (node (ref "R7") (pin "2") (pinfunction "2_2") (pintype "passive"))
      (node (ref "R70") (pin "2") (pinfunction "2_2") (pintype "passive"))
      (node (ref "R72") (pin "2") (pinfunction "2_2") (pintype "passive"))
      (node (ref "R74") (pin "2") (pinfunction "2_2") (pintype "passive"))
      (node (ref "R8") (pin "2") (pinfunction "2_2") (pintype "passive"))
      (node (ref "U$1") (pin "P$15") (pinfunction "A15_P$15") (pintype "bidirectional"))
      (node (ref "U$1") (pin "P$31") (pinfunction "A15_P$31") (pintype "bidirectional"))
      (node (ref "U1") (pin "VOUT") (pinfunction "OUT_VOUT") (pintype "passive"))
    )
    (net (code "11") (name "24V") (class "Default")
      (node (ref "D1") (pin "1") (pinfunction "K_1") (pintype "bidirectional"))
      (node (ref "D2") (pin "1") (pinfunction "K_1") (pintype "bidirectional"))
      (node (ref "D3") (pin "1") (pinfunction "K_1") (pintype "bidirectional"))
      (node (ref "D4") (pin "1") (pinfunction "K_1") (pintype "bidirectional"))
      (node (ref "J1") (pin "3") (pinfunction "3_3") (pintype "bidirectional"))
      (node (ref "J1") (pin "4") (pinfunction "4_4") (pintype "bidirectional"))
      (node (ref "J3") (pin "1") (pinfunction "1_1") (pintype "bidirectional"))
      (node (ref "J3") (pin "10") (pinfunction "10_10") (pintype "bidirectional"))
      (node (ref "J3") (pin "13") (pinfunction "13_13") (pintype "bidirectional"))
      (node (ref "J3") (pin "14") (pinfunction "14_14") (pintype "bidirectional"))
      (node (ref "J3") (pin "2") (pinfunction "2_2") (pintype "bidirectional"))
      (node (ref "J3") (pin "5") (pinfunction "5_5") (pintype "bidirectional"))
      (node (ref "J3") (pin "6") (pinfunction "6_6") (pintype "bidirectional"))
      (node (ref "J3") (pin "9") (pinfunction "9_9") (pintype "bidirectional"))
      (node (ref "R37") (pin "2") (pinfunction "2_2") (pintype "passive"))
      (node (ref "R38") (pin "2") (pinfunction "2_2") (pintype "passive"))
      (node (ref "R39") (pin "2") (pinfunction "2_2") (pintype "passive"))
      (node (ref "R40") (pin "2") (pinfunction "2_2") (pintype "passive"))
      (node (ref "R45") (pin "2") (pinfunction "2_2") (pintype "passive"))
      (node (ref "R46") (pin "2") (pinfunction "2_2") (pintype "passive"))
      (node (ref "R47") (pin "2") (pinfunction "2_2") (pintype "passive"))
      (node (ref "R48") (pin "2") (pinfunction "2_2") (pintype "passive"))
      (node (ref "U$1") (pin "P$16") (pinfunction "A16_P$16") (pintype "bidirectional"))
      (node (ref "U$1") (pin "P$32") (pinfunction "A16_P$32") (pintype "bidirectional"))
      (node (ref "U1") (pin "VIN") (pinfunction "IN_VIN") (pintype "input"))
    )
    (net (code "12") (name "A0") (class "Default")
      (node (ref "B1") (pin "A0") (pinfunction "A0(RX0)_A0") (pintype "bidirectional"))
      (node (ref "R73") (pin "1") (pinfunction "1_1") (pintype "passive"))
    )
    (net (code "13") (name "A1") (class "Default")
      (node (ref "B1") (pin "A1") (pinfunction "A1(TX0)_A1") (pintype "bidirectional"))
      (node (ref "R71") (pin "1") (pinfunction "1_1") (pintype "passive"))
    )
    (net (code "14") (name "A2") (class "Default")
      (node (ref "B1") (pin "A2") (pinfunction "A2_A2") (pintype "bidirectional"))
      (node (ref "R69") (pin "1") (pinfunction "1_1") (pintype "passive"))
    )
    (net (code "15") (name "A3") (class "Default")
      (node (ref "B1") (pin "A3") (pinfunction "A3_A3") (pintype "bidirectional"))
      (node (ref "R67") (pin "1") (pinfunction "1_1") (pintype "passive"))
    )
    (net (code "16") (name "A4") (class "Default")
      (node (ref "B1") (pin "A4") (pinfunction "A4_A4") (pintype "bidirectional"))
      (node (ref "U$1") (pin "P$13") (pinfunction "A13_P$13") (pintype "bidirectional"))
      (node (ref "U$1") (pin "P$29") (pinfunction "A13_P$29") (pintype "bidirectional"))
    )
    (net (code "17") (name "A5") (class "Default")
      (node (ref "B1") (pin "A5") (pinfunction "A5_A5") (pintype "bidirectional"))
      (node (ref "U$1") (pin "P$12") (pinfunction "A12_P$12") (pintype "bidirectional"))
      (node (ref "U$1") (pin "P$28") (pinfunction "A12_P$28") (pintype "bidirectional"))
    )
    (net (code "18") (name "A6") (class "Default")
      (node (ref "B1") (pin "A6") (pinfunction "A6_A6") (pintype "bidirectional"))
      (node (ref "U$1") (pin "P$11") (pinfunction "A11_P$11") (pintype "bidirectional"))
      (node (ref "U$1") (pin "P$27") (pinfunction "A11_P$27") (pintype "bidirectional"))
    )
    (net (code "19") (name "A7") (class "Default")
      (node (ref "B1") (pin "A7") (pinfunction "A7_A7") (pintype "bidirectional"))
      (node (ref "U$1") (pin "P$10") (pinfunction "A10_P$10") (pintype "bidirectional"))
      (node (ref "U$1") (pin "P$26") (pinfunction "A10_P$26") (pintype "bidirectional"))
    )
    (net (code "20") (name "A8") (class "Default")
      (node (ref "B1") (pin "A8") (pinfunction "A8_A8") (pintype "bidirectional"))
      (node (ref "U$1") (pin "P$25") (pinfunction "A9_P$25") (pintype "bidirectional"))
      (node (ref "U$1") (pin "P$9") (pinfunction "A9_P$9") (pintype "bidirectional"))
    )
    (net (code "21") (name "A9") (class "Default")
      (node (ref "B1") (pin "A9") (pinfunction "A9_A9") (pintype "bidirectional"))
      (node (ref "U$1") (pin "P$24") (pinfunction "A8_P$24") (pintype "bidirectional"))
      (node (ref "U$1") (pin "P$8") (pinfunction "A8_P$8") (pintype "bidirectional"))
    )
    (net (code "22") (name "AIN") (class "Default")
      (node (ref "J9") (pin "1") (pinfunction "1_1") (pintype "bidirectional"))
      (node (ref "J9") (pin "2") (pinfunction "2_2") (pintype "bidirectional"))
      (node (ref "R75") (pin "1") (pinfunction "1_1") (pintype "passive"))
    )
    (net (code "23") (name "DI0") (class "Default")
      (node (ref "B1") (pin "25") (pinfunction "25_25") (pintype "bidirectional"))
      (node (ref "IC1") (pin "16") (pinfunction "COLLECTOR_4_16") (pintype "bidirectional"))
      (node (ref "R5") (pin "1") (pinfunction "1_1") (pintype "passive"))
    )
    (net (code "24") (name "DI1") (class "Default")
      (node (ref "B1") (pin "26") (pinfunction "26_26") (pintype "bidirectional"))
      (node (ref "IC1") (pin "14") (pinfunction "COLLECTOR_3_14") (pintype "bidirectional"))
      (node (ref "R6") (pin "1") (pinfunction "1_1") (pintype "passive"))
    )
    (net (code "25") (name "DI2") (class "Default")
      (node (ref "B1") (pin "27") (pinfunction "27_27") (pintype "bidirectional"))
      (node (ref "IC1") (pin "12") (pinfunction "COLLECTOR_2_12") (pintype "bidirectional"))
      (node (ref "R7") (pin "1") (pinfunction "1_1") (pintype "passive"))
    )
    (net (code "26") (name "DI3") (class "Default")
      (node (ref "B1") (pin "28") (pinfunction "28_28") (pintype "bidirectional"))
      (node (ref "IC1") (pin "10") (pinfunction "COLLECTOR_1_10") (pintype "bidirectional"))
      (node (ref "R8") (pin "1") (pinfunction "1_1") (pintype "passive"))
    )
    (net (code "27") (name "DI4") (class "Default")
      (node (ref "B1") (pin "29") (pinfunction "29_29") (pintype "bidirectional"))
      (node (ref "IC2") (pin "16") (pinfunction "COLLECTOR_4_16") (pintype "bidirectional"))
      (node (ref "R13") (pin "1") (pinfunction "1_1") (pintype "passive"))
    )
    (net (code "28") (name "DI5") (class "Default")
      (node (ref "B1") (pin "30") (pinfunction "30_30") (pintype "bidirectional"))
      (node (ref "IC2") (pin "14") (pinfunction "COLLECTOR_3_14") (pintype "bidirectional"))
      (node (ref "R14") (pin "1") (pinfunction "1_1") (pintype "passive"))
    )
    (net (code "29") (name "DI6") (class "Default")
      (node (ref "B1") (pin "31") (pinfunction "31_31") (pintype "bidirectional"))
      (node (ref "IC2") (pin "12") (pinfunction "COLLECTOR_2_12") (pintype "bidirectional"))
      (node (ref "R15") (pin "1") (pinfunction "1_1") (pintype "passive"))
    )
    (net (code "30") (name "DI7") (class "Default")
      (node (ref "B1") (pin "32") (pinfunction "32_32") (pintype "bidirectional"))
      (node (ref "IC2") (pin "10") (pinfunction "COLLECTOR_1_10") (pintype "bidirectional"))
      (node (ref "R16") (pin "1") (pinfunction "1_1") (pintype "passive"))
    )
    (net (code "31") (name "DI8") (class "Default")
      (node (ref "B1") (pin "33") (pinfunction "33_33") (pintype "bidirectional"))
      (node (ref "IC3") (pin "16") (pinfunction "COLLECTOR_4_16") (pintype "bidirectional"))
      (node (ref "R21") (pin "1") (pinfunction "1_1") (pintype "passive"))
    )
    (net (code "32") (name "DI9") (class "Default")
      (node (ref "B1") (pin "34") (pinfunction "34_34") (pintype "bidirectional"))
      (node (ref "IC3") (pin "14") (pinfunction "COLLECTOR_3_14") (pintype "bidirectional"))
      (node (ref "R22") (pin "1") (pinfunction "1_1") (pintype "passive"))
    )
    (net (code "33") (name "DI10") (class "Default")
      (node (ref "B1") (pin "35") (pinfunction "35_35") (pintype "bidirectional"))
      (node (ref "IC3") (pin "12") (pinfunction "COLLECTOR_2_12") (pintype "bidirectional"))
      (node (ref "R23") (pin "1") (pinfunction "1_1") (pintype "passive"))
    )
    (net (code "34") (name "DI11") (class "Default")
      (node (ref "B1") (pin "36") (pinfunction "36_36") (pintype "bidirectional"))
      (node (ref "IC3") (pin "10") (pinfunction "COLLECTOR_1_10") (pintype "bidirectional"))
      (node (ref "R24") (pin "1") (pinfunction "1_1") (pintype "passive"))
    )
    (net (code "35") (name "DI12") (class "Default")
      (node (ref "B1") (pin "37") (pinfunction "37_37") (pintype "bidirectional"))
      (node (ref "IC4") (pin "16") (pinfunction "COLLECTOR_4_16") (pintype "bidirectional"))
      (node (ref "R29") (pin "1") (pinfunction "1_1") (pintype "passive"))
    )
    (net (code "36") (name "DI13") (class "Default")
      (node (ref "B1") (pin "38") (pinfunction "38_38") (pintype "bidirectional"))
      (node (ref "IC4") (pin "14") (pinfunction "COLLECTOR_3_14") (pintype "bidirectional"))
      (node (ref "R30") (pin "1") (pinfunction "1_1") (pintype "passive"))
    )
    (net (code "37") (name "DI14") (class "Default")
      (node (ref "B1") (pin "39") (pinfunction "39_39") (pintype "bidirectional"))
      (node (ref "IC4") (pin "12") (pinfunction "COLLECTOR_2_12") (pintype "bidirectional"))
      (node (ref "R31") (pin "1") (pinfunction "1_1") (pintype "passive"))
    )
    (net (code "38") (name "DI15") (class "Default")
      (node (ref "B1") (pin "40") (pinfunction "40_40") (pintype "bidirectional"))
      (node (ref "IC4") (pin "10") (pinfunction "COLLECTOR_1_10") (pintype "bidirectional"))
      (node (ref "R32") (pin "1") (pinfunction "1_1") (pintype "passive"))
    )
    (net (code "39") (name "DIR") (class "Default")
      (node (ref "B1") (pin "24") (pinfunction "24_24") (pintype "bidirectional"))
      (node (ref "J2") (pin "3") (pinfunction "3_3") (pintype "bidirectional"))
      (node (ref "J2") (pin "4") (pinfunction "4_4") (pintype "bidirectional"))
    )
    (net (code "40") (name "DO0") (class "Default")
      (node (ref "B1") (pin "44") (pinfunction "44_44") (pintype "bidirectional"))
      (node (ref "R33") (pin "1") (pinfunction "1_1") (pintype "passive"))
    )
    (net (code "41") (name "DO1") (class "Default")
      (node (ref "B1") (pin "45") (pinfunction "45_45") (pintype "bidirectional"))
      (node (ref "R34") (pin "1") (pinfunction "1_1") (pintype "passive"))
    )
    (net (code "42") (name "DO2") (class "Default")
      (node (ref "B1") (pin "42") (pinfunction "42_42") (pintype "bidirectional"))
      (node (ref "R35") (pin "1") (pinfunction "1_1") (pintype "passive"))
    )
    (net (code "43") (name "DO3") (class "Default")
      (node (ref "B1") (pin "43") (pinfunction "43_43") (pintype "bidirectional"))
      (node (ref "R36") (pin "1") (pinfunction "1_1") (pintype "passive"))
    )
    (net (code "44") (name "DO4") (class "Default")
      (node (ref "B1") (pin "49") (pinfunction "49_49") (pintype "bidirectional"))
      (node (ref "R41") (pin "1") (pinfunction "1_1") (pintype "passive"))
    )
    (net (code "45") (name "DO5") (class "Default")
      (node (ref "B1") (pin "48") (pinfunction "48_48") (pintype "bidirectional"))
      (node (ref "R42") (pin "1") (pinfunction "1_1") (pintype "passive"))
    )
    (net (code "46") (name "DO6") (class "Default")
      (node (ref "B1") (pin "46") (pinfunction "46_46") (pintype "bidirectional"))
      (node (ref "R43") (pin "1") (pinfunction "1_1") (pintype "passive"))
    )
    (net (code "47") (name "DO7") (class "Default")
      (node (ref "B1") (pin "47") (pinfunction "47_47") (pintype "bidirectional"))
      (node (ref "R44") (pin "1") (pinfunction "1_1") (pintype "passive"))
    )
    (net (code "48") (name "ENBL") (class "Default")
      (node (ref "B1") (pin "23") (pinfunction "23_23") (pintype "bidirectional"))
      (node (ref "J2") (pin "5") (pinfunction "5_5") (pintype "bidirectional"))
      (node (ref "J2") (pin "6") (pinfunction "6_6") (pintype "bidirectional"))
    )
    (net (code "49") (name "GND") (class "Default")
      (node (ref "B1") (pin "GND@0") (pinfunction "GND_GND@0") (pintype "bidirectional"))
      (node (ref "B1") (pin "GND@1") (pinfunction "GND_GND@1") (pintype "bidirectional"))
      (node (ref "B1") (pin "GND@2") (pinfunction "GND_GND@2") (pintype "bidirectional"))
      (node (ref "B1") (pin "GND@3") (pinfunction "GND_GND@3") (pintype "bidirectional"))
      (node (ref "B1") (pin "GND@4") (pinfunction "GND_GND@4") (pintype "bidirectional"))
      (node (ref "C1") (pin "2") (pinfunction "2_2") (pintype "passive"))
      (node (ref "C3") (pin "2") (pinfunction "2_2") (pintype "passive"))
      (node (ref "C6") (pin "2") (pinfunction "2_2") (pintype "passive"))
      (node (ref "IC1") (pin "11") (pinfunction "EMITTER_2_11") (pintype "bidirectional"))
      (node (ref "IC1") (pin "13") (pinfunction "EMITTER_3_13") (pintype "bidirectional"))
      (node (ref "IC1") (pin "15") (pinfunction "EMITTER_4_15") (pintype "bidirectional"))
      (node (ref "IC1") (pin "9") (pinfunction "EMITTER_1_9") (pintype "bidirectional"))
      (node (ref "IC2") (pin "11") (pinfunction "EMITTER_2_11") (pintype "bidirectional"))
      (node (ref "IC2") (pin "13") (pinfunction "EMITTER_3_13") (pintype "bidirectional"))
      (node (ref "IC2") (pin "15") (pinfunction "EMITTER_4_15") (pintype "bidirectional"))
      (node (ref "IC2") (pin "9") (pinfunction "EMITTER_1_9") (pintype "bidirectional"))
      (node (ref "IC3") (pin "11") (pinfunction "EMITTER_2_11") (pintype "bidirectional"))
      (node (ref "IC3") (pin "13") (pinfunction "EMITTER_3_13") (pintype "bidirectional"))
      (node (ref "IC3") (pin "15") (pinfunction "EMITTER_4_15") (pintype "bidirectional"))
      (node (ref "IC3") (pin "9") (pinfunction "EMITTER_1_9") (pintype "bidirectional"))
      (node (ref "IC4") (pin "11") (pinfunction "EMITTER_2_11") (pintype "bidirectional"))
      (node (ref "IC4") (pin "13") (pinfunction "EMITTER_3_13") (pintype "bidirectional"))
      (node (ref "IC4") (pin "15") (pinfunction "EMITTER_4_15") (pintype "bidirectional"))
      (node (ref "IC4") (pin "9") (pinfunction "EMITTER_1_9") (pintype "bidirectional"))
      (node (ref "IC5") (pin "2") (pinfunction "ANODE,CATHODE_1_2") (pintype "bidirectional"))
      (node (ref "IC5") (pin "4") (pinfunction "ANODE,CATHODE_2_4") (pintype "bidirectional"))
      (node (ref "IC5") (pin "6") (pinfunction "ANODE,CATHODE_3_6") (pintype "bidirectional"))
      (node (ref "IC5") (pin "8") (pinfunction "ANODE,CATHODE_4_8") (pintype "bidirectional"))
      (node (ref "IC6") (pin "2") (pinfunction "ANODE,CATHODE_1_2") (pintype "bidirectional"))
      (node (ref "IC6") (pin "4") (pinfunction "ANODE,CATHODE_2_4") (pintype "bidirectional"))
      (node (ref "IC6") (pin "6") (pinfunction "ANODE,CATHODE_3_6") (pintype "bidirectional"))
      (node (ref "IC6") (pin "8") (pinfunction "ANODE,CATHODE_4_8") (pintype "bidirectional"))
      (node (ref "IC7") (pin "3") (pinfunction "GND_3") (pintype "bidirectional"))
      (node (ref "J1") (pin "1") (pinfunction "1_1") (pintype "bidirectional"))
      (node (ref "J1") (pin "2") (pinfunction "2_2") (pintype "bidirectional"))
      (node (ref "J2") (pin "7") (pinfunction "7_7") (pintype "bidirectional"))
      (node (ref "J2") (pin "8") (pinfunction "8_8") (pintype "bidirectional"))
      (node (ref "J8") (pin "17") (pinfunction "17_17") (pintype "bidirectional"))
      (node (ref "J8") (pin "18") (pinfunction "18_18") (pintype "bidirectional"))
      (node (ref "J9") (pin "3") (pinfunction "3_3") (pintype "bidirectional"))
      (node (ref "J9") (pin "4") (pinfunction "4_4") (pintype "bidirectional"))
      (node (ref "JP1") (pin "1") (pinfunction "1_1") (pintype "passive"))
      (node (ref "JP3") (pin "1") (pinfunction "1_1") (pintype "passive"))
      (node (ref "Q1") (pin "2") (pinfunction "S_2") (pintype "bidirectional"))
      (node (ref "Q2") (pin "2") (pinfunction "S_2") (pintype "bidirectional"))
      (node (ref "Q3") (pin "2") (pinfunction "S_2") (pintype "bidirectional"))
      (node (ref "Q4") (pin "2") (pinfunction "S_2") (pintype "bidirectional"))
      (node (ref "Q5") (pin "E") (pinfunction "E_E") (pintype "passive"))
      (node (ref "Q6") (pin "E") (pinfunction "E_E") (pintype "passive"))
      (node (ref "Q7") (pin "E") (pinfunction "E_E") (pintype "passive"))
      (node (ref "Q8") (pin "E") (pinfunction "E_E") (pintype "passive"))
      (node (ref "R49") (pin "1") (pinfunction "1_1") (pintype "passive"))
      (node (ref "R50") (pin "1") (pinfunction "1_1") (pintype "passive"))
      (node (ref "R51") (pin "1") (pinfunction "1_1") (pintype "passive"))
      (node (ref "R52") (pin "1") (pinfunction "1_1") (pintype "passive"))
      (node (ref "R53") (pin "1") (pinfunction "1_1") (pintype "passive"))
      (node (ref "R54") (pin "1") (pinfunction "1_1") (pintype "passive"))
      (node (ref "R55") (pin "1") (pinfunction "1_1") (pintype "passive"))
      (node (ref "R56") (pin "1") (pinfunction "1_1") (pintype "passive"))
      (node (ref "R59") (pin "1") (pinfunction "1_1") (pintype "passive"))
      (node (ref "R61") (pin "1") (pinfunction "1_1") (pintype "passive"))
      (node (ref "R63") (pin "1") (pinfunction "1_1") (pintype "passive"))
      (node (ref "R65") (pin "1") (pinfunction "1_1") (pintype "passive"))
      (node (ref "R76") (pin "1") (pinfunction "1_1") (pintype "passive"))
      (node (ref "R77") (pin "1") (pinfunction "1_1") (pintype "passive"))
      (node (ref "U$1") (pin "P$1") (pinfunction "A1_P$1") (pintype "bidirectional"))
      (node (ref "U$1") (pin "P$17") (pinfunction "A1_P$17") (pintype "bidirectional"))
      (node (ref "U1") (pin "GND") (pinfunction "GND_GND") (pintype "input"))
      (node (ref "U2") (pin "1") (pinfunction "GND_1") (pintype "bidirectional"))
      (node (ref "U3") (pin "1") (pinfunction "GND_1") (pintype "bidirectional"))
    )
    (net (code "50") (name "MISO") (class "Default")
      (node (ref "B1") (pin "50") (pinfunction "50_50") (pintype "bidirectional"))
      (node (ref "JP1") (pin "4") (pinfunction "4_4") (pintype "passive"))
      (node (ref "JP3") (pin "4") (pinfunction "4_4") (pintype "passive"))
      (node (ref "U2") (pin "7") (pinfunction "(MI)SO_7") (pintype "bidirectional"))
      (node (ref "U3") (pin "7") (pinfunction "(MI)SO_7") (pintype "bidirectional"))
    )
    (net (code "51") (name "MOSI") (class "Default")
      (node (ref "B1") (pin "51") (pinfunction "51_51") (pintype "bidirectional"))
    )
    (net (code "52") (name "MS0-") (class "Default")
      (node (ref "D1") (pin "2") (pinfunction "A_2") (pintype "bidirectional"))
      (node (ref "J3") (pin "3") (pinfunction "3_3") (pintype "bidirectional"))
      (node (ref "J3") (pin "4") (pinfunction "4_4") (pintype "bidirectional"))
      (node (ref "Q1") (pin "3") (pinfunction "D_3") (pintype "bidirectional"))
    )
    (net (code "53") (name "MS1-") (class "Default")
      (node (ref "D2") (pin "2") (pinfunction "A_2") (pintype "bidirectional"))
      (node (ref "J3") (pin "7") (pinfunction "7_7") (pintype "bidirectional"))
      (node (ref "J3") (pin "8") (pinfunction "8_8") (pintype "bidirectional"))
      (node (ref "Q2") (pin "3") (pinfunction "D_3") (pintype "bidirectional"))
    )
    (net (code "54") (name "MS2-") (class "Default")
      (node (ref "D3") (pin "2") (pinfunction "A_2") (pintype "bidirectional"))
      (node (ref "J3") (pin "11") (pinfunction "11_11") (pintype "bidirectional"))
      (node (ref "J3") (pin "12") (pinfunction "12_12") (pintype "bidirectional"))
      (node (ref "Q3") (pin "3") (pinfunction "D_3") (pintype "bidirectional"))
    )
    (net (code "55") (name "MS3-") (class "Default")
      (node (ref "D4") (pin "2") (pinfunction "A_2") (pintype "bidirectional"))
      (node (ref "J3") (pin "15") (pinfunction "15_15") (pintype "bidirectional"))
      (node (ref "J3") (pin "16") (pinfunction "16_16") (pintype "bidirectional"))
      (node (ref "Q4") (pin "3") (pinfunction "D_3") (pintype "bidirectional"))
    )
    (net (code "56") (name "Net-(IC1-CATHODE,ANODE_1)") (class "Default")
      (node (ref "IC1") (pin "1") (pinfunction "CATHODE,ANODE_1_1") (pintype "bidirectional"))
      (node (ref "R1") (pin "2") (pinfunction "2_2") (pintype "passive"))
    )
    (net (code "57") (name "Net-(IC1-CATHODE,ANODE_2)") (class "Default")
      (node (ref "IC1") (pin "3") (pinfunction "CATHODE,ANODE_2_3") (pintype "bidirectional"))
      (node (ref "R2") (pin "2") (pinfunction "2_2") (pintype "passive"))
    )
    (net (code "58") (name "Net-(IC1-CATHODE,ANODE_3)") (class "Default")
      (node (ref "IC1") (pin "5") (pinfunction "CATHODE,ANODE_3_5") (pintype "bidirectional"))
      (node (ref "R3") (pin "2") (pinfunction "2_2") (pintype "passive"))
    )
    (net (code "59") (name "Net-(IC1-CATHODE,ANODE_4)") (class "Default")
      (node (ref "IC1") (pin "7") (pinfunction "CATHODE,ANODE_4_7") (pintype "bidirectional"))
      (node (ref "R4") (pin "2") (pinfunction "2_2") (pintype "passive"))
    )
    (net (code "60") (name "Net-(IC2-CATHODE,ANODE_1)") (class "Default")
      (node (ref "IC2") (pin "1") (pinfunction "CATHODE,ANODE_1_1") (pintype "bidirectional"))
      (node (ref "R9") (pin "2") (pinfunction "2_2") (pintype "passive"))
    )
    (net (code "61") (name "Net-(IC2-CATHODE,ANODE_2)") (class "Default")
      (node (ref "IC2") (pin "3") (pinfunction "CATHODE,ANODE_2_3") (pintype "bidirectional"))
      (node (ref "R10") (pin "2") (pinfunction "2_2") (pintype "passive"))
    )
    (net (code "62") (name "Net-(IC2-CATHODE,ANODE_3)") (class "Default")
      (node (ref "IC2") (pin "5") (pinfunction "CATHODE,ANODE_3_5") (pintype "bidirectional"))
      (node (ref "R11") (pin "2") (pinfunction "2_2") (pintype "passive"))
    )
    (net (code "63") (name "Net-(IC2-CATHODE,ANODE_4)") (class "Default")
      (node (ref "IC2") (pin "7") (pinfunction "CATHODE,ANODE_4_7") (pintype "bidirectional"))
      (node (ref "R12") (pin "2") (pinfunction "2_2") (pintype "passive"))
    )
    (net (code "64") (name "Net-(IC3-CATHODE,ANODE_1)") (class "Default")
      (node (ref "IC3") (pin "1") (pinfunction "CATHODE,ANODE_1_1") (pintype "bidirectional"))
      (node (ref "R17") (pin "2") (pinfunction "2_2") (pintype "passive"))
    )
    (net (code "65") (name "Net-(IC3-CATHODE,ANODE_2)") (class "Default")
      (node (ref "IC3") (pin "3") (pinfunction "CATHODE,ANODE_2_3") (pintype "bidirectional"))
      (node (ref "R18") (pin "2") (pinfunction "2_2") (pintype "passive"))
    )
    (net (code "66") (name "Net-(IC3-CATHODE,ANODE_3)") (class "Default")
      (node (ref "IC3") (pin "5") (pinfunction "CATHODE,ANODE_3_5") (pintype "bidirectional"))
      (node (ref "R19") (pin "2") (pinfunction "2_2") (pintype "passive"))
    )
    (net (code "67") (name "Net-(IC3-CATHODE,ANODE_4)") (class "Default")
      (node (ref "IC3") (pin "7") (pinfunction "CATHODE,ANODE_4_7") (pintype "bidirectional"))
      (node (ref "R20") (pin "2") (pinfunction "2_2") (pintype "passive"))
    )
    (net (code "68") (name "Net-(IC4-CATHODE,ANODE_1)") (class "Default")
      (node (ref "IC4") (pin "1") (pinfunction "CATHODE,ANODE_1_1") (pintype "bidirectional"))
      (node (ref "R25") (pin "2") (pinfunction "2_2") (pintype "passive"))
    )
    (net (code "69") (name "Net-(IC4-CATHODE,ANODE_2)") (class "Default")
      (node (ref "IC4") (pin "3") (pinfunction "CATHODE,ANODE_2_3") (pintype "bidirectional"))
      (node (ref "R26") (pin "2") (pinfunction "2_2") (pintype "passive"))
    )
    (net (code "70") (name "Net-(IC4-CATHODE,ANODE_3)") (class "Default")
      (node (ref "IC4") (pin "5") (pinfunction "CATHODE,ANODE_3_5") (pintype "bidirectional"))
      (node (ref "R27") (pin "2") (pinfunction "2_2") (pintype "passive"))
    )
    (net (code "71") (name "Net-(IC4-CATHODE,ANODE_4)") (class "Default")
      (node (ref "IC4") (pin "7") (pinfunction "CATHODE,ANODE_4_7") (pintype "bidirectional"))
      (node (ref "R28") (pin "2") (pinfunction "2_2") (pintype "passive"))
    )
    (net (code "72") (name "Net-(IC5-CATHODE,ANODE_1)") (class "Default")
      (node (ref "IC5") (pin "1") (pinfunction "CATHODE,ANODE_1_1") (pintype "bidirectional"))
      (node (ref "R33") (pin "2") (pinfunction "2_2") (pintype "passive"))
    )
    (net (code "73") (name "Net-(IC5-CATHODE,ANODE_2)") (class "Default")
      (node (ref "IC5") (pin "3") (pinfunction "CATHODE,ANODE_2_3") (pintype "bidirectional"))
      (node (ref "R34") (pin "2") (pinfunction "2_2") (pintype "passive"))
    )
    (net (code "74") (name "Net-(IC5-CATHODE,ANODE_3)") (class "Default")
      (node (ref "IC5") (pin "5") (pinfunction "CATHODE,ANODE_3_5") (pintype "bidirectional"))
      (node (ref "R35") (pin "2") (pinfunction "2_2") (pintype "passive"))
    )
    (net (code "75") (name "Net-(IC5-CATHODE,ANODE_4)") (class "Default")
      (node (ref "IC5") (pin "7") (pinfunction "CATHODE,ANODE_4_7") (pintype "bidirectional"))
      (node (ref "R36") (pin "2") (pinfunction "2_2") (pintype "passive"))
    )
    (net (code "76") (name "Net-(IC5-EMITTER_1)") (class "Default")
      (node (ref "IC5") (pin "9") (pinfunction "EMITTER_1_9") (pintype "bidirectional"))
      (node (ref "R52") (pin "2") (pinfunction "2_2") (pintype "passive"))
    )
    (net (code "77") (name "Net-(IC5-EMITTER_2)") (class "Default")
      (node (ref "IC5") (pin "11") (pinfunction "EMITTER_2_11") (pintype "bidirectional"))
      (node (ref "R51") (pin "2") (pinfunction "2_2") (pintype "passive"))
    )
    (net (code "78") (name "Net-(IC5-EMITTER_3)") (class "Default")
      (node (ref "IC5") (pin "13") (pinfunction "EMITTER_3_13") (pintype "bidirectional"))
      (node (ref "R50") (pin "2") (pinfunction "2_2") (pintype "passive"))
    )
    (net (code "79") (name "Net-(IC5-EMITTER_4)") (class "Default")
      (node (ref "IC5") (pin "15") (pinfunction "EMITTER_4_15") (pintype "bidirectional"))
      (node (ref "R49") (pin "2") (pinfunction "2_2") (pintype "passive"))
    )
    (net (code "80") (name "Net-(IC6-CATHODE,ANODE_1)") (class "Default")
      (node (ref "IC6") (pin "1") (pinfunction "CATHODE,ANODE_1_1") (pintype "bidirectional"))
      (node (ref "R41") (pin "2") (pinfunction "2_2") (pintype "passive"))
    )
    (net (code "81") (name "Net-(IC6-CATHODE,ANODE_2)") (class "Default")
      (node (ref "IC6") (pin "3") (pinfunction "CATHODE,ANODE_2_3") (pintype "bidirectional"))
      (node (ref "R42") (pin "2") (pinfunction "2_2") (pintype "passive"))
    )
    (net (code "82") (name "Net-(IC6-CATHODE,ANODE_3)") (class "Default")
      (node (ref "IC6") (pin "5") (pinfunction "CATHODE,ANODE_3_5") (pintype "bidirectional"))
      (node (ref "R43") (pin "2") (pinfunction "2_2") (pintype "passive"))
    )
    (net (code "83") (name "Net-(IC6-CATHODE,ANODE_4)") (class "Default")
      (node (ref "IC6") (pin "7") (pinfunction "CATHODE,ANODE_4_7") (pintype "bidirectional"))
      (node (ref "R44") (pin "2") (pinfunction "2_2") (pintype "passive"))
    )
    (net (code "84") (name "Net-(IC6-EMITTER_1)") (class "Default")
      (node (ref "IC6") (pin "9") (pinfunction "EMITTER_1_9") (pintype "bidirectional"))
      (node (ref "R56") (pin "2") (pinfunction "2_2") (pintype "passive"))
    )
    (net (code "85") (name "Net-(IC6-EMITTER_2)") (class "Default")
      (node (ref "IC6") (pin "11") (pinfunction "EMITTER_2_11") (pintype "bidirectional"))
      (node (ref "R55") (pin "2") (pinfunction "2_2") (pintype "passive"))
    )
    (net (code "86") (name "Net-(IC6-EMITTER_3)") (class "Default")
      (node (ref "IC6") (pin "13") (pinfunction "EMITTER_3_13") (pintype "bidirectional"))
      (node (ref "R54") (pin "2") (pinfunction "2_2") (pintype "passive"))
    )
    (net (code "87") (name "Net-(IC6-EMITTER_4)") (class "Default")
      (node (ref "IC6") (pin "15") (pinfunction "EMITTER_4_15") (pintype "bidirectional"))
      (node (ref "R53") (pin "2") (pinfunction "2_2") (pintype "passive"))
    )
    (net (code "88") (name "Net-(IC7-ADDR)") (class "Default")
      (node (ref "IC7") (pin "1") (pinfunction "ADDR_1") (pintype "bidirectional"))
      (node (ref "R77") (pin "2") (pinfunction "2_2") (pintype "passive"))
    )
    (net (code "89") (name "Net-(IC7-AIN0)") (class "Default")
      (node (ref "C6") (pin "1") (pinfunction "1_1") (pintype "passive"))
      (node (ref "IC7") (pin "4") (pinfunction "AIN0_4") (pintype "bidirectional"))
      (node (ref "R75") (pin "2") (pinfunction "2_2") (pintype "passive"))
      (node (ref "R76") (pin "2") (pinfunction "2_2") (pintype "passive"))
    )
    (net (code "90") (name "Net-(IC7-SCL)") (class "Default")
      (node (ref "IC7") (pin "10") (pinfunction "SCL_10") (pintype "bidirectional"))
      (node (ref "R78") (pin "2") (pinfunction "2_2") (pintype "passive"))
    )
    (net (code "91") (name "Net-(IC7-SDA)") (class "Default")
      (node (ref "IC7") (pin "9") (pinfunction "SDA_9") (pintype "bidirectional"))
      (node (ref "R79") (pin "2") (pinfunction "2_2") (pintype "passive"))
    )
    (net (code "92") (name "Net-(IC7-VDD)") (class "Default")
      (node (ref "C5") (pin "2") (pinfunction "2_2") (pintype "passive"))
      (node (ref "IC7") (pin "8") (pinfunction "VDD_8") (pintype "bidirectional"))
    )
    (net (code "93") (name "Net-(K1--INPUT)") (class "Default")
      (node (ref "K1") (pin "4") (pinfunction "-INPUT_4") (pintype "bidirectional"))
      (node (ref "LED1") (pin "C") (pinfunction "C_C") (pintype "passive"))
      (node (ref "Q5") (pin "C") (pinfunction "C_C") (pintype "passive"))
    )
    (net (code "94") (name "Net-(K2--INPUT)") (class "Default")
      (node (ref "K2") (pin "4") (pinfunction "-INPUT_4") (pintype "bidirectional"))
      (node (ref "LED2") (pin "C") (pinfunction "C_C") (pintype "passive"))
      (node (ref "Q6") (pin "C") (pinfunction "C_C") (pintype "passive"))
    )
    (net (code "95") (name "Net-(K3--INPUT)") (class "Default")
      (node (ref "K3") (pin "4") (pinfunction "-INPUT_4") (pintype "bidirectional"))
      (node (ref "LED3") (pin "C") (pinfunction "C_C") (pintype "passive"))
      (node (ref "Q7") (pin "C") (pinfunction "C_C") (pintype "passive"))
    )
    (net (code "96") (name "Net-(K4--INPUT)") (class "Default")
      (node (ref "K4") (pin "4") (pinfunction "-INPUT_4") (pintype "bidirectional"))
      (node (ref "LED4") (pin "C") (pinfunction "C_C") (pintype "passive"))
      (node (ref "Q8") (pin "C") (pinfunction "C_C") (pintype "passive"))
    )
    (net (code "97") (name "Net-(LED1-PadA)") (class "Default")
      (node (ref "LED1") (pin "A") (pinfunction "A_A") (pintype "passive"))
      (node (ref "R68") (pin "1") (pinfunction "1_1") (pintype "passive"))
    )
    (net (code "98") (name "Net-(LED2-PadA)") (class "Default")
      (node (ref "LED2") (pin "A") (pinfunction "A_A") (pintype "passive"))
      (node (ref "R70") (pin "1") (pinfunction "1_1") (pintype "passive"))
    )
    (net (code "99") (name "Net-(LED3-PadA)") (class "Default")
      (node (ref "LED3") (pin "A") (pinfunction "A_A") (pintype "passive"))
      (node (ref "R72") (pin "1") (pinfunction "1_1") (pintype "passive"))
    )
    (net (code "100") (name "Net-(LED4-PadA)") (class "Default")
      (node (ref "LED4") (pin "A") (pinfunction "A_A") (pintype "passive"))
      (node (ref "R74") (pin "1") (pinfunction "1_1") (pintype "passive"))
    )
    (net (code "101") (name "Net-(Q1-G)") (class "Default")
      (node (ref "Q1") (pin "1") (pinfunction "G_1") (pintype "bidirectional"))
      (node (ref "R60") (pin "2") (pinfunction "2_2") (pintype "passive"))
    )
    (net (code "102") (name "Net-(Q2-G)") (class "Default")
      (node (ref "Q2") (pin "1") (pinfunction "G_1") (pintype "bidirectional"))
      (node (ref "R62") (pin "2") (pinfunction "2_2") (pintype "passive"))
    )
    (net (code "103") (name "Net-(Q3-G)") (class "Default")
      (node (ref "Q3") (pin "1") (pinfunction "G_1") (pintype "bidirectional"))
      (node (ref "R64") (pin "2") (pinfunction "2_2") (pintype "passive"))
    )
    (net (code "104") (name "Net-(Q4-G)") (class "Default")
      (node (ref "Q4") (pin "1") (pinfunction "G_1") (pintype "bidirectional"))
      (node (ref "R66") (pin "2") (pinfunction "2_2") (pintype "passive"))
    )
    (net (code "105") (name "Net-(Q5-PadB)") (class "Default")
      (node (ref "Q5") (pin "B") (pinfunction "B_B") (pintype "passive"))
      (node (ref "R67") (pin "2") (pinfunction "2_2") (pintype "passive"))
    )
    (net (code "106") (name "Net-(Q6-PadB)") (class "Default")
      (node (ref "Q6") (pin "B") (pinfunction "B_B") (pintype "passive"))
      (node (ref "R69") (pin "2") (pinfunction "2_2") (pintype "passive"))
    )
    (net (code "107") (name "Net-(Q7-PadB)") (class "Default")
      (node (ref "Q7") (pin "B") (pinfunction "B_B") (pintype "passive"))
      (node (ref "R71") (pin "2") (pinfunction "2_2") (pintype "passive"))
    )
    (net (code "108") (name "Net-(Q8-PadB)") (class "Default")
      (node (ref "Q8") (pin "B") (pinfunction "B_B") (pintype "passive"))
      (node (ref "R73") (pin "2") (pinfunction "2_2") (pintype "passive"))
    )
    (net (code "109") (name "Net-(U2-T+)") (class "Default")
      (node (ref "C2") (pin "1") (pinfunction "1_1") (pintype "passive"))
      (node (ref "L2") (pin "1") (pinfunction "1_1") (pintype "passive"))
      (node (ref "U2") (pin "3") (pinfunction "T+_3") (pintype "bidirectional"))
    )
    (net (code "110") (name "Net-(U2-T-)") (class "Default")
      (node (ref "C2") (pin "2") (pinfunction "2_2") (pintype "passive"))
      (node (ref "L1") (pin "1") (pinfunction "1_1") (pintype "passive"))
      (node (ref "U2") (pin "2") (pinfunction "T-_2") (pintype "bidirectional"))
    )
    (net (code "111") (name "Net-(U3-T+)") (class "Default")
      (node (ref "C4") (pin "1") (pinfunction "1_1") (pintype "passive"))
      (node (ref "L4") (pin "1") (pinfunction "1_1") (pintype "passive"))
      (node (ref "U3") (pin "3") (pinfunction "T+_3") (pintype "bidirectional"))
    )
    (net (code "112") (name "Net-(U3-T-)") (class "Default")
      (node (ref "C4") (pin "2") (pinfunction "2_2") (pintype "passive"))
      (node (ref "L3") (pin "1") (pinfunction "1_1") (pintype "passive"))
      (node (ref "U3") (pin "2") (pinfunction "T-_2") (pintype "bidirectional"))
    )
    (net (code "113") (name "PLC_COM1") (class "Default")
      (node (ref "IC1") (pin "2") (pinfunction "ANODE,CATHODE_1_2") (pintype "bidirectional"))
      (node (ref "IC1") (pin "4") (pinfunction "ANODE,CATHODE_2_4") (pintype "bidirectional"))
      (node (ref "IC1") (pin "6") (pinfunction "ANODE,CATHODE_3_6") (pintype "bidirectional"))
      (node (ref "IC1") (pin "8") (pinfunction "ANODE,CATHODE_4_8") (pintype "bidirectional"))
      (node (ref "IC2") (pin "2") (pinfunction "ANODE,CATHODE_1_2") (pintype "bidirectional"))
      (node (ref "IC2") (pin "4") (pinfunction "ANODE,CATHODE_2_4") (pintype "bidirectional"))
      (node (ref "IC2") (pin "6") (pinfunction "ANODE,CATHODE_3_6") (pintype "bidirectional"))
      (node (ref "IC2") (pin "8") (pinfunction "ANODE,CATHODE_4_8") (pintype "bidirectional"))
      (node (ref "J6") (pin "17") (pinfunction "17_17") (pintype "bidirectional"))
      (node (ref "J6") (pin "18") (pinfunction "18_18") (pintype "bidirectional"))
    )
    (net (code "114") (name "PLC_COM2") (class "Default")
      (node (ref "IC3") (pin "2") (pinfunction "ANODE,CATHODE_1_2") (pintype "bidirectional"))
      (node (ref "IC3") (pin "4") (pinfunction "ANODE,CATHODE_2_4") (pintype "bidirectional"))
      (node (ref "IC3") (pin "6") (pinfunction "ANODE,CATHODE_3_6") (pintype "bidirectional"))
      (node (ref "IC3") (pin "8") (pinfunction "ANODE,CATHODE_4_8") (pintype "bidirectional"))
      (node (ref "IC4") (pin "2") (pinfunction "ANODE,CATHODE_1_2") (pintype "bidirectional"))
      (node (ref "IC4") (pin "4") (pinfunction "ANODE,CATHODE_2_4") (pintype "bidirectional"))
      (node (ref "IC4") (pin "6") (pinfunction "ANODE,CATHODE_3_6") (pintype "bidirectional"))
      (node (ref "IC4") (pin "8") (pinfunction "ANODE,CATHODE_4_8") (pintype "bidirectional"))
      (node (ref "J7") (pin "17") (pinfunction "17_17") (pintype "bidirectional"))
      (node (ref "J7") (pin "18") (pinfunction "18_18") (pintype "bidirectional"))
    )
    (net (code "115") (name "PLC_DI0") (class "Default")
      (node (ref "J6") (pin "1") (pinfunction "1_1") (pintype "bidirectional"))
      (node (ref "J6") (pin "2") (pinfunction "2_2") (pintype "bidirectional"))
      (node (ref "R1") (pin "1") (pinfunction "1_1") (pintype "passive"))
    )
    (net (code "116") (name "PLC_DI1") (class "Default")
      (node (ref "J6") (pin "3") (pinfunction "3_3") (pintype "bidirectional"))
      (node (ref "J6") (pin "4") (pinfunction "4_4") (pintype "bidirectional"))
      (node (ref "R2") (pin "1") (pinfunction "1_1") (pintype "passive"))
    )
    (net (code "117") (name "PLC_DI2") (class "Default")
      (node (ref "J6") (pin "5") (pinfunction "5_5") (pintype "bidirectional"))
      (node (ref "J6") (pin "6") (pinfunction "6_6") (pintype "bidirectional"))
      (node (ref "R3") (pin "1") (pinfunction "1_1") (pintype "passive"))
    )
    (net (code "118") (name "PLC_DI3") (class "Default")
      (node (ref "J6") (pin "7") (pinfunction "7_7") (pintype "bidirectional"))
      (node (ref "J6") (pin "8") (pinfunction "8_8") (pintype "bidirectional"))
      (node (ref "R4") (pin "1") (pinfunction "1_1") (pintype "passive"))
    )
    (net (code "119") (name "PLC_DI4") (class "Default")
      (node (ref "J6") (pin "10") (pinfunction "10_10") (pintype "bidirectional"))
      (node (ref "J6") (pin "9") (pinfunction "9_9") (pintype "bidirectional"))
      (node (ref "R9") (pin "1") (pinfunction "1_1") (pintype "passive"))
    )
    (net (code "120") (name "PLC_DI5") (class "Default")
      (node (ref "J6") (pin "11") (pinfunction "11_11") (pintype "bidirectional"))
      (node (ref "J6") (pin "12") (pinfunction "12_12") (pintype "bidirectional"))
      (node (ref "R10") (pin "1") (pinfunction "1_1") (pintype "passive"))
    )
    (net (code "121") (name "PLC_DI6") (class "Default")
      (node (ref "J6") (pin "13") (pinfunction "13_13") (pintype "bidirectional"))
      (node (ref "J6") (pin "14") (pinfunction "14_14") (pintype "bidirectional"))
      (node (ref "R11") (pin "1") (pinfunction "1_1") (pintype "passive"))
    )
    (net (code "122") (name "PLC_DI7") (class "Default")
      (node (ref "J6") (pin "15") (pinfunction "15_15") (pintype "bidirectional"))
      (node (ref "J6") (pin "16") (pinfunction "16_16") (pintype "bidirectional"))
      (node (ref "R12") (pin "1") (pinfunction "1_1") (pintype "passive"))
    )
    (net (code "123") (name "PLC_DI8") (class "Default")
      (node (ref "J7") (pin "1") (pinfunction "1_1") (pintype "bidirectional"))
      (node (ref "J7") (pin "2") (pinfunction "2_2") (pintype "bidirectional"))
      (node (ref "R17") (pin "1") (pinfunction "1_1") (pintype "passive"))
    )
    (net (code "124") (name "PLC_DI9") (class "Default")
      (node (ref "J7") (pin "3") (pinfunction "3_3") (pintype "bidirectional"))
      (node (ref "J7") (pin "4") (pinfunction "4_4") (pintype "bidirectional"))
      (node (ref "R18") (pin "1") (pinfunction "1_1") (pintype "passive"))
    )
    (net (code "125") (name "PLC_DI10") (class "Default")
      (node (ref "J7") (pin "5") (pinfunction "5_5") (pintype "bidirectional"))
      (node (ref "J7") (pin "6") (pinfunction "6_6") (pintype "bidirectional"))
      (node (ref "R19") (pin "1") (pinfunction "1_1") (pintype "passive"))
    )
    (net (code "126") (name "PLC_DI11") (class "Default")
      (node (ref "J7") (pin "7") (pinfunction "7_7") (pintype "bidirectional"))
      (node (ref "J7") (pin "8") (pinfunction "8_8") (pintype "bidirectional"))
      (node (ref "R20") (pin "1") (pinfunction "1_1") (pintype "passive"))
    )
    (net (code "127") (name "PLC_DI12") (class "Default")
      (node (ref "J7") (pin "10") (pinfunction "10_10") (pintype "bidirectional"))
      (node (ref "J7") (pin "9") (pinfunction "9_9") (pintype "bidirectional"))
      (node (ref "R25") (pin "1") (pinfunction "1_1") (pintype "passive"))
    )
    (net (code "128") (name "PLC_DI13") (class "Default")
      (node (ref "J7") (pin "11") (pinfunction "11_11") (pintype "bidirectional"))
      (node (ref "J7") (pin "12") (pinfunction "12_12") (pintype "bidirectional"))
      (node (ref "R26") (pin "1") (pinfunction "1_1") (pintype "passive"))
    )
    (net (code "129") (name "PLC_DI14") (class "Default")
      (node (ref "J7") (pin "13") (pinfunction "13_13") (pintype "bidirectional"))
      (node (ref "J7") (pin "14") (pinfunction "14_14") (pintype "bidirectional"))
      (node (ref "R27") (pin "1") (pinfunction "1_1") (pintype "passive"))
    )
    (net (code "130") (name "PLC_DI15") (class "Default")
      (node (ref "J7") (pin "15") (pinfunction "15_15") (pintype "bidirectional"))
      (node (ref "J7") (pin "16") (pinfunction "16_16") (pintype "bidirectional"))
      (node (ref "R28") (pin "1") (pinfunction "1_1") (pintype "passive"))
    )
    (net (code "131") (name "PLC_DO0") (class "Default")
      (node (ref "IC5") (pin "16") (pinfunction "COLLECTOR_4_16") (pintype "bidirectional"))
      (node (ref "J8") (pin "7") (pinfunction "7_7") (pintype "bidirectional"))
      (node (ref "J8") (pin "8") (pinfunction "8_8") (pintype "bidirectional"))
      (node (ref "R37") (pin "1") (pinfunction "1_1") (pintype "passive"))
    )
    (net (code "132") (name "PLC_DO1") (class "Default")
      (node (ref "IC5") (pin "14") (pinfunction "COLLECTOR_3_14") (pintype "bidirectional"))
      (node (ref "J8") (pin "5") (pinfunction "5_5") (pintype "bidirectional"))
      (node (ref "J8") (pin "6") (pinfunction "6_6") (pintype "bidirectional"))
      (node (ref "R38") (pin "1") (pinfunction "1_1") (pintype "passive"))
    )
    (net (code "133") (name "PLC_DO2") (class "Default")
      (node (ref "IC5") (pin "12") (pinfunction "COLLECTOR_2_12") (pintype "bidirectional"))
      (node (ref "J8") (pin "3") (pinfunction "3_3") (pintype "bidirectional"))
      (node (ref "J8") (pin "4") (pinfunction "4_4") (pintype "bidirectional"))
      (node (ref "R39") (pin "1") (pinfunction "1_1") (pintype "passive"))
    )
    (net (code "134") (name "PLC_DO3") (class "Default")
      (node (ref "IC5") (pin "10") (pinfunction "COLLECTOR_1_10") (pintype "bidirectional"))
      (node (ref "J8") (pin "1") (pinfunction "1_1") (pintype "bidirectional"))
      (node (ref "J8") (pin "2") (pinfunction "2_2") (pintype "bidirectional"))
      (node (ref "R40") (pin "1") (pinfunction "1_1") (pintype "passive"))
    )
    (net (code "135") (name "PLC_DO4") (class "Default")
      (node (ref "IC6") (pin "16") (pinfunction "COLLECTOR_4_16") (pintype "bidirectional"))
      (node (ref "J8") (pin "15") (pinfunction "15_15") (pintype "bidirectional"))
      (node (ref "J8") (pin "16") (pinfunction "16_16") (pintype "bidirectional"))
      (node (ref "R45") (pin "1") (pinfunction "1_1") (pintype "passive"))
    )
    (net (code "136") (name "PLC_DO5") (class "Default")
      (node (ref "IC6") (pin "14") (pinfunction "COLLECTOR_3_14") (pintype "bidirectional"))
      (node (ref "J8") (pin "13") (pinfunction "13_13") (pintype "bidirectional"))
      (node (ref "J8") (pin "14") (pinfunction "14_14") (pintype "bidirectional"))
      (node (ref "R46") (pin "1") (pinfunction "1_1") (pintype "passive"))
    )
    (net (code "137") (name "PLC_DO6") (class "Default")
      (node (ref "IC6") (pin "12") (pinfunction "COLLECTOR_2_12") (pintype "bidirectional"))
      (node (ref "J8") (pin "11") (pinfunction "11_11") (pintype "bidirectional"))
      (node (ref "J8") (pin "12") (pinfunction "12_12") (pintype "bidirectional"))
      (node (ref "R47") (pin "1") (pinfunction "1_1") (pintype "passive"))
    )
    (net (code "138") (name "PLC_DO7") (class "Default")
      (node (ref "IC6") (pin "10") (pinfunction "COLLECTOR_1_10") (pintype "bidirectional"))
      (node (ref "J8") (pin "10") (pinfunction "10_10") (pintype "bidirectional"))
      (node (ref "J8") (pin "9") (pinfunction "9_9") (pintype "bidirectional"))
      (node (ref "R48") (pin "1") (pinfunction "1_1") (pintype "passive"))
    )
    (net (code "139") (name "PWM0") (class "Default")
      (node (ref "B1") (pin "0") (pinfunction "0(RX0)_0") (pintype "bidirectional"))
      (node (ref "U$1") (pin "P$18") (pinfunction "A2_P$18") (pintype "bidirectional"))
      (node (ref "U$1") (pin "P$2") (pinfunction "A2_P$2") (pintype "bidirectional"))
    )
    (net (code "140") (name "PWM1") (class "Default")
      (node (ref "B1") (pin "1") (pinfunction "1(TX0)_1") (pintype "bidirectional"))
      (node (ref "U$1") (pin "P$19") (pinfunction "A3_P$19") (pintype "bidirectional"))
      (node (ref "U$1") (pin "P$3") (pinfunction "A3_P$3") (pintype "bidirectional"))
    )
    (net (code "141") (name "PWM2") (class "Default")
      (node (ref "B1") (pin "2") (pinfunction "2_2") (pintype "bidirectional"))
      (node (ref "U$1") (pin "P$20") (pinfunction "A4_P$20") (pintype "bidirectional"))
      (node (ref "U$1") (pin "P$4") (pinfunction "A4_P$4") (pintype "bidirectional"))
    )
    (net (code "142") (name "PWM3") (class "Default")
      (node (ref "B1") (pin "3") (pinfunction "3_3") (pintype "bidirectional"))
      (node (ref "U$1") (pin "P$21") (pinfunction "A5_P$21") (pintype "bidirectional"))
      (node (ref "U$1") (pin "P$5") (pinfunction "A5_P$5") (pintype "bidirectional"))
    )
    (net (code "143") (name "PWM4") (class "Default")
      (node (ref "B1") (pin "4") (pinfunction "4_4") (pintype "bidirectional"))
      (node (ref "U$1") (pin "P$22") (pinfunction "A6_P$22") (pintype "bidirectional"))
      (node (ref "U$1") (pin "P$6") (pinfunction "A6_P$6") (pintype "bidirectional"))
    )
    (net (code "144") (name "PWM5") (class "Default")
      (node (ref "B1") (pin "5") (pinfunction "5_5") (pintype "bidirectional"))
      (node (ref "U$1") (pin "P$23") (pinfunction "A7_P$23") (pintype "bidirectional"))
      (node (ref "U$1") (pin "P$7") (pinfunction "A7_P$7") (pintype "bidirectional"))
    )
    (net (code "145") (name "PWM10") (class "Default")
      (node (ref "B1") (pin "10") (pinfunction "10_10") (pintype "bidirectional"))
      (node (ref "R65") (pin "2") (pinfunction "2_2") (pintype "passive"))
      (node (ref "R66") (pin "1") (pinfunction "1_1") (pintype "passive"))
    )
    (net (code "146") (name "PWM11") (class "Default")
      (node (ref "B1") (pin "11") (pinfunction "11_11") (pintype "bidirectional"))
      (node (ref "R63") (pin "2") (pinfunction "2_2") (pintype "passive"))
      (node (ref "R64") (pin "1") (pinfunction "1_1") (pintype "passive"))
    )
    (net (code "147") (name "PWM12") (class "Default")
      (node (ref "B1") (pin "12") (pinfunction "12_12") (pintype "bidirectional"))
      (node (ref "R61") (pin "2") (pinfunction "2_2") (pintype "passive"))
      (node (ref "R62") (pin "1") (pinfunction "1_1") (pintype "passive"))
    )
    (net (code "148") (name "PWM13") (class "Default")
      (node (ref "B1") (pin "13") (pinfunction "13_13") (pintype "bidirectional"))
      (node (ref "R59") (pin "2") (pinfunction "2_2") (pintype "passive"))
      (node (ref "R60") (pin "1") (pinfunction "1_1") (pintype "passive"))
    )
    (net (code "149") (name "SCK") (class "Default")
      (node (ref "B1") (pin "52") (pinfunction "52_52") (pintype "bidirectional"))
      (node (ref "JP1") (pin "3") (pinfunction "3_3") (pintype "passive"))
      (node (ref "JP3") (pin "3") (pinfunction "3_3") (pintype "passive"))
      (node (ref "U2") (pin "5") (pinfunction "SCK_5") (pintype "bidirectional"))
      (node (ref "U3") (pin "5") (pinfunction "SCK_5") (pintype "bidirectional"))
    )
    (net (code "150") (name "SCL") (class "Default")
      (node (ref "B1") (pin "21") (pinfunction "21(SCL)_21") (pintype "bidirectional"))
      (node (ref "R78") (pin "1") (pinfunction "1_1") (pintype "passive"))
    )
    (net (code "151") (name "SDA") (class "Default")
      (node (ref "B1") (pin "20") (pinfunction "20(SDA)_20") (pintype "bidirectional"))
      (node (ref "R79") (pin "1") (pinfunction "1_1") (pintype "passive"))
    )
    (net (code "152") (name "SS") (class "Default")
      (node (ref "B1") (pin "53") (pinfunction "53_53") (pintype "bidirectional"))
    )
    (net (code "153") (name "STEP") (class "Default")
      (node (ref "B1") (pin "22") (pinfunction "22_22") (pintype "bidirectional"))
      (node (ref "J2") (pin "1") (pinfunction "1_1") (pintype "bidirectional"))
      (node (ref "J2") (pin "2") (pinfunction "2_2") (pintype "bidirectional"))
    )
    (net (code "154") (name "T1+") (class "Default")
      (node (ref "J5") (pin "3") (pinfunction "3_3") (pintype "bidirectional"))
      (node (ref "J5") (pin "4") (pinfunction "4_4") (pintype "bidirectional"))
      (node (ref "JP2") (pin "+") (pinfunction "+_+") (pintype "passive"))
      (node (ref "L2") (pin "2") (pinfunction "2_2") (pintype "passive"))
    )
    (net (code "155") (name "T1-") (class "Default")
      (node (ref "J5") (pin "1") (pinfunction "1_1") (pintype "bidirectional"))
      (node (ref "J5") (pin "2") (pinfunction "2_2") (pintype "bidirectional"))
      (node (ref "JP2") (pin "-") (pinfunction "-_-") (pintype "passive"))
      (node (ref "L1") (pin "2") (pinfunction "2_2") (pintype "passive"))
    )
    (net (code "156") (name "T1_CS") (class "Default")
      (node (ref "B1") (pin "19") (pinfunction "19(RX1)_19") (pintype "bidirectional"))
      (node (ref "JP1") (pin "6") (pinfunction "6_6") (pintype "passive"))
      (node (ref "R57") (pin "1") (pinfunction "1_1") (pintype "passive"))
      (node (ref "U2") (pin "6") (pinfunction "~{CS}_6") (pintype "bidirectional"))
    )
    (net (code "157") (name "T2+") (class "Default")
      (node (ref "J5") (pin "7") (pinfunction "7_7") (pintype "bidirectional"))
      (node (ref "J5") (pin "8") (pinfunction "8_8") (pintype "bidirectional"))
      (node (ref "JP4") (pin "+") (pinfunction "+_+") (pintype "passive"))
      (node (ref "L4") (pin "2") (pinfunction "2_2") (pintype "passive"))
    )
    (net (code "158") (name "T2-") (class "Default")
      (node (ref "J5") (pin "5") (pinfunction "5_5") (pintype "bidirectional"))
      (node (ref "J5") (pin "6") (pinfunction "6_6") (pintype "bidirectional"))
      (node (ref "JP4") (pin "-") (pinfunction "-_-") (pintype "passive"))
      (node (ref "L3") (pin "2") (pinfunction "2_2") (pintype "passive"))
    )
    (net (code "159") (name "T2_CS") (class "Default")
      (node (ref "B1") (pin "18") (pinfunction "18(TX1)_18") (pintype "bidirectional"))
      (node (ref "JP3") (pin "6") (pinfunction "6_6") (pintype "passive"))
      (node (ref "R58") (pin "1") (pinfunction "1_1") (pintype "passive"))
      (node (ref "U3") (pin "6") (pinfunction "~{CS}_6") (pintype "bidirectional"))
    )
    (net (code "160") (name "unconnected-(B1-5V-Pad5V@0)") (class "Default")
      (node (ref "B1") (pin "5V@0") (pinfunction "5V_5V@0") (pintype "bidirectional"))
    )
    (net (code "161") (name "unconnected-(B1-5V-Pad5V@1)") (class "Default")
      (node (ref "B1") (pin "5V@1") (pinfunction "5V_5V@1") (pintype "bidirectional"))
    )
    (net (code "162") (name "unconnected-(B1-5V-Pad5V@2)") (class "Default")
      (node (ref "B1") (pin "5V@2") (pinfunction "5V_5V@2") (pintype "bidirectional"))
    )
    (net (code "163") (name "unconnected-(B1-14(TX3)-Pad14)") (class "Default")
      (node (ref "B1") (pin "14") (pinfunction "14(TX3)_14") (pintype "bidirectional"))
    )
    (net (code "164") (name "unconnected-(B1-15(RX3)-Pad15)") (class "Default")
      (node (ref "B1") (pin "15") (pinfunction "15(RX3)_15") (pintype "bidirectional"))
    )
    (net (code "165") (name "unconnected-(B1-16(TX2)-Pad16)") (class "Default")
      (node (ref "B1") (pin "16") (pinfunction "16(TX2)_16") (pintype "bidirectional"))
    )
    (net (code "166") (name "unconnected-(B1-17(RX2)-Pad17)") (class "Default")
      (node (ref "B1") (pin "17") (pinfunction "17(RX2)_17") (pintype "bidirectional"))
    )
    (net (code "167") (name "unconnected-(B1-Pad6)") (class "Default")
      (node (ref "B1") (pin "6") (pinfunction "6_6") (pintype "bidirectional"))
    )
    (net (code "168") (name "unconnected-(B1-Pad7)") (class "Default")
      (node (ref "B1") (pin "7") (pinfunction "7_7") (pintype "bidirectional"))
    )
    (net (code "169") (name "unconnected-(B1-Pad8)") (class "Default")
      (node (ref "B1") (pin "8") (pinfunction "8_8") (pintype "bidirectional"))
    )
    (net (code "170") (name "unconnected-(B1-Pad9)") (class "Default")
      (node (ref "B1") (pin "9") (pinfunction "9_9") (pintype "bidirectional"))
    )
    (net (code "171") (name "unconnected-(B1-Pad41)") (class "Default")
      (node (ref "B1") (pin "41") (pinfunction "41_41") (pintype "bidirectional"))
    )
    (net (code "172") (name "unconnected-(B1-PadA10)") (class "Default")
      (node (ref "B1") (pin "A10") (pinfunction "A10_A10") (pintype "bidirectional"))
    )
    (net (code "173") (name "unconnected-(B1-PadA11)") (class "Default")
      (node (ref "B1") (pin "A11") (pinfunction "A11_A11") (pintype "bidirectional"))
    )
    (net (code "174") (name "unconnected-(B1-PadA12)") (class "Default")
      (node (ref "B1") (pin "A12") (pinfunction "A12_A12") (pintype "bidirectional"))
    )
    (net (code "175") (name "unconnected-(B1-PadA13)") (class "Default")
      (node (ref "B1") (pin "A13") (pinfunction "A13_A13") (pintype "bidirectional"))
    )
    (net (code "176") (name "unconnected-(B1-PadA14)") (class "Default")
      (node (ref "B1") (pin "A14") (pinfunction "A14_A14") (pintype "bidirectional"))
    )
    (net (code "177") (name "unconnected-(B1-PadA15)") (class "Default")
      (node (ref "B1") (pin "A15") (pinfunction "A15_A15") (pintype "bidirectional"))
    )
    (net (code "178") (name "unconnected-(B1-PadAREF)") (class "Default")
      (node (ref "B1") (pin "AREF") (pinfunction "AREF_AREF") (pintype "bidirectional"))
    )
    (net (code "179") (name "unconnected-(B1-PadRESET)") (class "Default")
      (node (ref "B1") (pin "RESET") (pinfunction "RESET_RESET") (pintype "bidirectional"))
    )
    (net (code "180") (name "unconnected-(IC7-AIN1-Pad5)") (class "Default")
      (node (ref "IC7") (pin "5") (pinfunction "AIN1_5") (pintype "bidirectional"))
    )
    (net (code "181") (name "unconnected-(IC7-AIN2-Pad6)") (class "Default")
      (node (ref "IC7") (pin "6") (pinfunction "AIN2_6") (pintype "bidirectional"))
    )
    (net (code "182") (name "unconnected-(IC7-AIN3-Pad7)") (class "Default")
      (node (ref "IC7") (pin "7") (pinfunction "AIN3_7") (pintype "bidirectional"))
    )
    (net (code "183") (name "unconnected-(IC7-ALERT{slash}RDY-Pad2)") (class "Default")
      (node (ref "IC7") (pin "2") (pinfunction "ALERT/RDY_2") (pintype "bidirectional"))
    )
    (net (code "184") (name "unconnected-(JP1-Pad5)") (class "Default")
      (node (ref "JP1") (pin "5") (pinfunction "5_5") (pintype "passive"))
    )
    (net (code "185") (name "unconnected-(JP3-Pad5)") (class "Default")
      (node (ref "JP3") (pin "5") (pinfunction "5_5") (pintype "passive"))
    )
  )
)
